# DigitMux.net
KiCad netlist of a schematic drawn in EAGLE
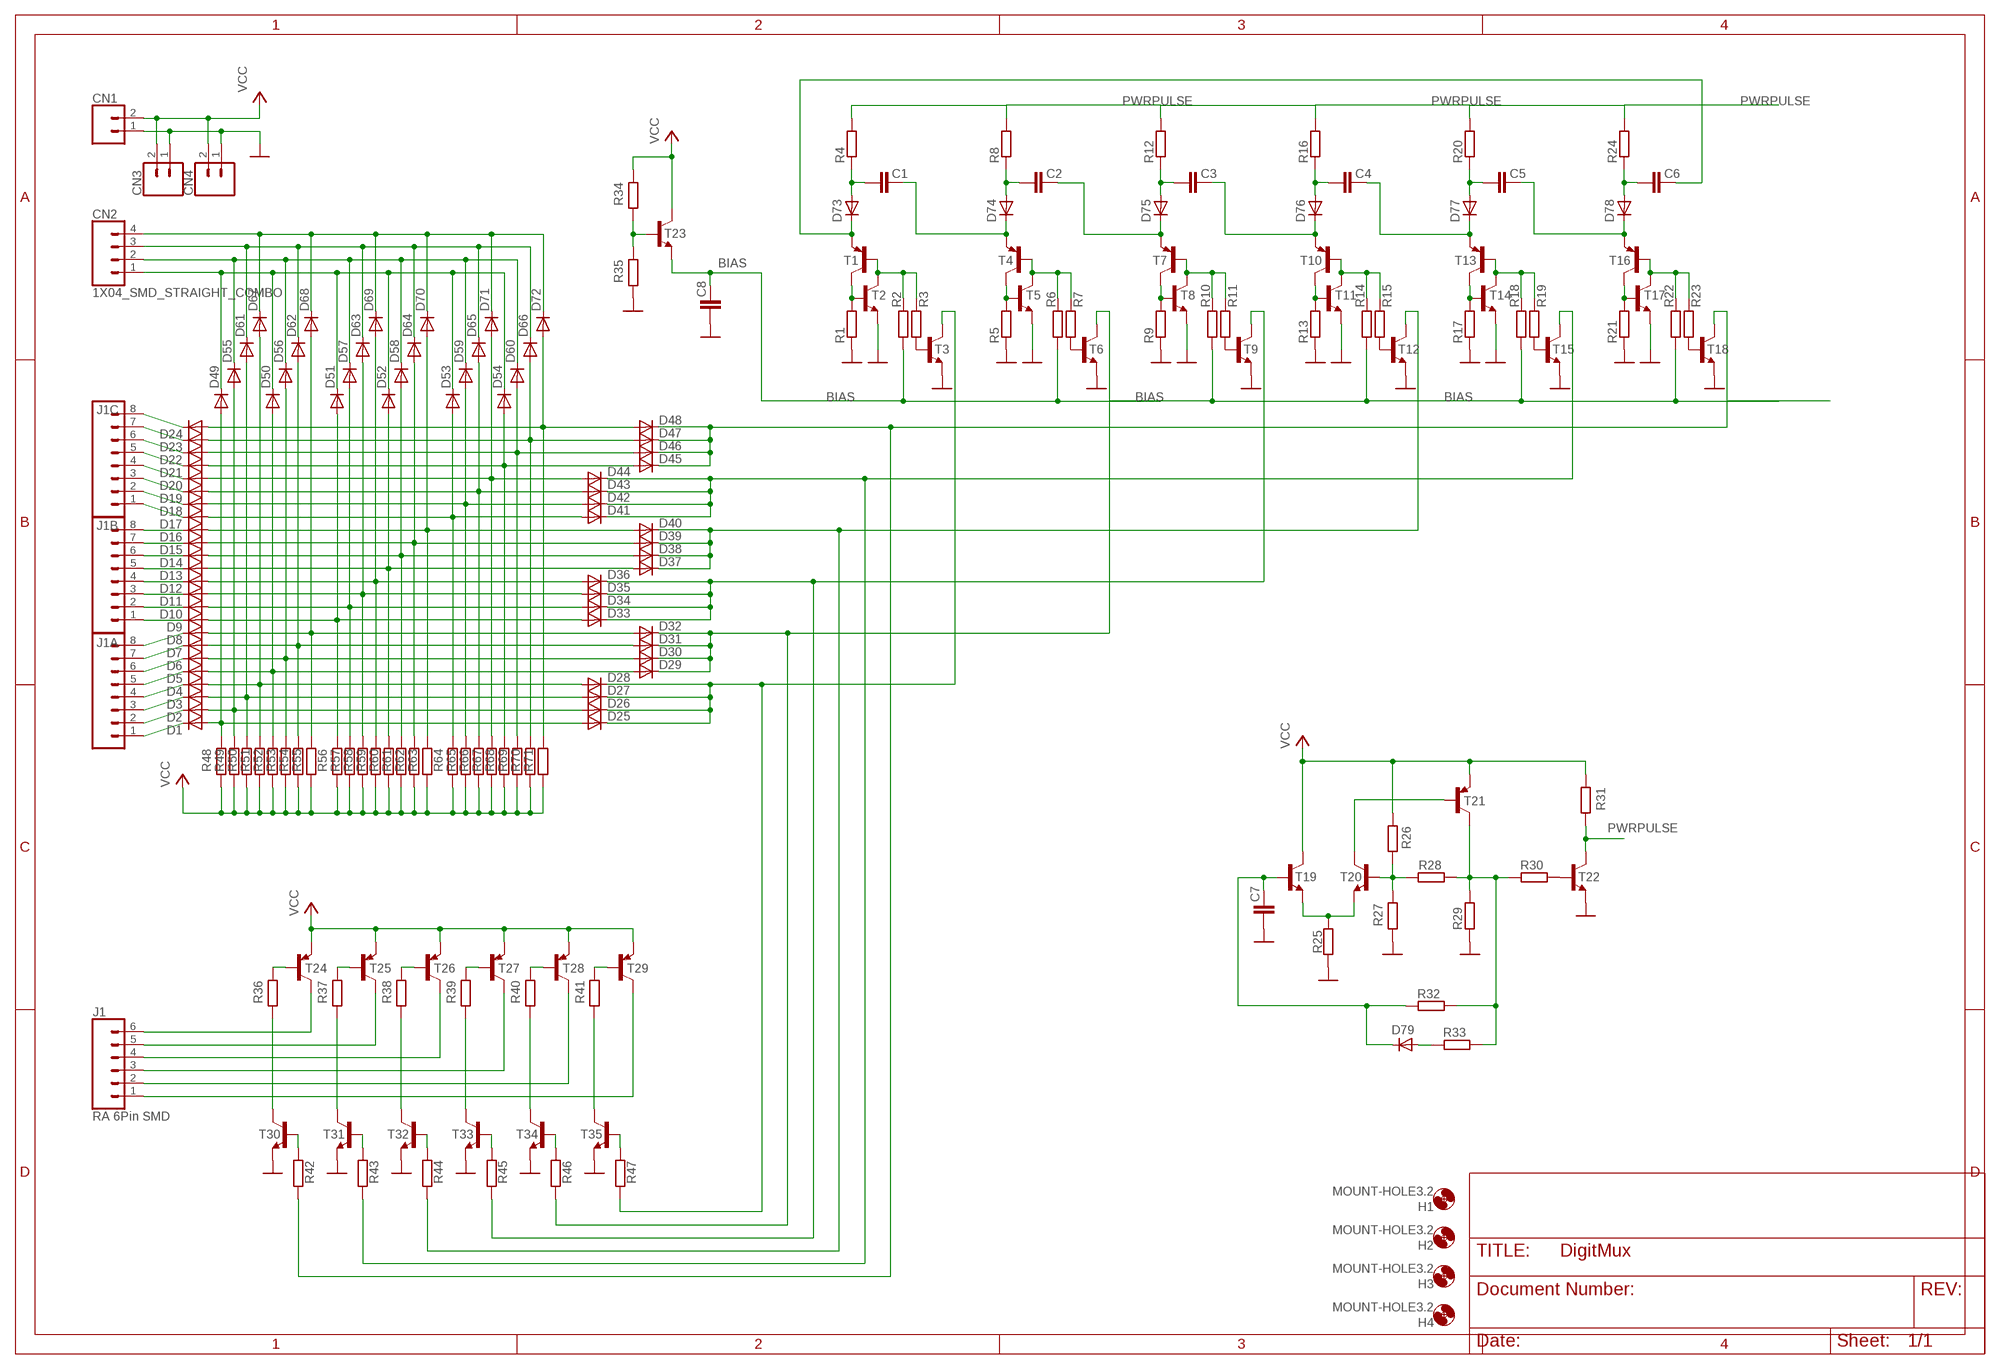
[diagram p0: schematic, sheet 1]

(export (version "E")
  (design (tool "Eeschema 10.0.6"))
  (components
    (comp (ref "C1")
      (value "0.1uF")
      (footprint "eagle-import:CAP-PTH-SMALL-KIT")
      (libsource (lib "eagle-import") (part "0.1UF-KIT-EZ-50V-20%"))
    )
    (comp (ref "C2")
      (value "0.1uF")
      (footprint "eagle-import:CAP-PTH-SMALL-KIT")
      (libsource (lib "eagle-import") (part "0.1UF-KIT-EZ-50V-20%"))
    )
    (comp (ref "C3")
      (value "0.1uF")
      (footprint "eagle-import:CAP-PTH-SMALL-KIT")
      (libsource (lib "eagle-import") (part "0.1UF-KIT-EZ-50V-20%"))
    )
    (comp (ref "C4")
      (value "0.1uF")
      (footprint "eagle-import:CAP-PTH-SMALL-KIT")
      (libsource (lib "eagle-import") (part "0.1UF-KIT-EZ-50V-20%"))
    )
    (comp (ref "C5")
      (value "0.1uF")
      (footprint "eagle-import:CAP-PTH-SMALL-KIT")
      (libsource (lib "eagle-import") (part "0.1UF-KIT-EZ-50V-20%"))
    )
    (comp (ref "C6")
      (value "0.1uF")
      (footprint "eagle-import:CAP-PTH-SMALL-KIT")
      (libsource (lib "eagle-import") (part "0.1UF-KIT-EZ-50V-20%"))
    )
    (comp (ref "C7")
      (value "0.1uF")
      (footprint "eagle-import:CAP-PTH-SMALL-KIT")
      (libsource (lib "eagle-import") (part "0.1UF-KIT-EZ-50V-20%"))
    )
    (comp (ref "C8")
      (value "0.1uF")
      (footprint "eagle-import:CAP-PTH-SMALL-KIT")
      (libsource (lib "eagle-import") (part "0.1UF-KIT-EZ-50V-20%"))
    )
    (comp (ref "CN1")
      (value "CONN_02")
      (footprint "eagle-import:1X02")
      (libsource (lib "eagle-import") (part "CONN_02"))
    )
    (comp (ref "CN2")
      (value "1X04_SMD_STRAIGHT_COMBO")
      (footprint "eagle-import:1X04")
      (libsource (lib "eagle-import") (part "CONN_04"))
    )
    (comp (ref "CN3")
      (value "CONN_02")
      (footprint "eagle-import:1X02")
      (libsource (lib "eagle-import") (part "CONN_02"))
    )
    (comp (ref "CN4")
      (value "CONN_02")
      (footprint "eagle-import:1X02")
      (libsource (lib "eagle-import") (part "CONN_02"))
    )
    (comp (ref "D1")
      (value "SMALL_DIODEDO35-7")
      (footprint "eagle-import:DO35-7")
      (libsource (lib "eagle-import") (part "SMALL_DIODEDO35-7"))
    )
    (comp (ref "D2")
      (value "SMALL_DIODEDO35-7")
      (footprint "eagle-import:DO35-7")
      (libsource (lib "eagle-import") (part "SMALL_DIODEDO35-7"))
    )
    (comp (ref "D3")
      (value "SMALL_DIODEDO35-7")
      (footprint "eagle-import:DO35-7")
      (libsource (lib "eagle-import") (part "SMALL_DIODEDO35-7"))
    )
    (comp (ref "D4")
      (value "SMALL_DIODEDO35-7")
      (footprint "eagle-import:DO35-7")
      (libsource (lib "eagle-import") (part "SMALL_DIODEDO35-7"))
    )
    (comp (ref "D5")
      (value "SMALL_DIODEDO35-7")
      (footprint "eagle-import:DO35-7")
      (libsource (lib "eagle-import") (part "SMALL_DIODEDO35-7"))
    )
    (comp (ref "D6")
      (value "SMALL_DIODEDO35-7")
      (footprint "eagle-import:DO35-7")
      (libsource (lib "eagle-import") (part "SMALL_DIODEDO35-7"))
    )
    (comp (ref "D7")
      (value "SMALL_DIODEDO35-7")
      (footprint "eagle-import:DO35-7")
      (libsource (lib "eagle-import") (part "SMALL_DIODEDO35-7"))
    )
    (comp (ref "D8")
      (value "SMALL_DIODEDO35-7")
      (footprint "eagle-import:DO35-7")
      (libsource (lib "eagle-import") (part "SMALL_DIODEDO35-7"))
    )
    (comp (ref "D9")
      (value "SMALL_DIODEDO35-7")
      (footprint "eagle-import:DO35-7")
      (libsource (lib "eagle-import") (part "SMALL_DIODEDO35-7"))
    )
    (comp (ref "D10")
      (value "SMALL_DIODEDO35-7")
      (footprint "eagle-import:DO35-7")
      (libsource (lib "eagle-import") (part "SMALL_DIODEDO35-7"))
    )
    (comp (ref "D11")
      (value "SMALL_DIODEDO35-7")
      (footprint "eagle-import:DO35-7")
      (libsource (lib "eagle-import") (part "SMALL_DIODEDO35-7"))
    )
    (comp (ref "D12")
      (value "SMALL_DIODEDO35-7")
      (footprint "eagle-import:DO35-7")
      (libsource (lib "eagle-import") (part "SMALL_DIODEDO35-7"))
    )
    (comp (ref "D13")
      (value "SMALL_DIODEDO35-7")
      (footprint "eagle-import:DO35-7")
      (libsource (lib "eagle-import") (part "SMALL_DIODEDO35-7"))
    )
    (comp (ref "D14")
      (value "SMALL_DIODEDO35-7")
      (footprint "eagle-import:DO35-7")
      (libsource (lib "eagle-import") (part "SMALL_DIODEDO35-7"))
    )
    (comp (ref "D15")
      (value "SMALL_DIODEDO35-7")
      (footprint "eagle-import:DO35-7")
      (libsource (lib "eagle-import") (part "SMALL_DIODEDO35-7"))
    )
    (comp (ref "D16")
      (value "SMALL_DIODEDO35-7")
      (footprint "eagle-import:DO35-7")
      (libsource (lib "eagle-import") (part "SMALL_DIODEDO35-7"))
    )
    (comp (ref "D17")
      (value "SMALL_DIODEDO35-7")
      (footprint "eagle-import:DO35-7")
      (libsource (lib "eagle-import") (part "SMALL_DIODEDO35-7"))
    )
    (comp (ref "D18")
      (value "SMALL_DIODEDO35-7")
      (footprint "eagle-import:DO35-7")
      (libsource (lib "eagle-import") (part "SMALL_DIODEDO35-7"))
    )
    (comp (ref "D19")
      (value "SMALL_DIODEDO35-7")
      (footprint "eagle-import:DO35-7")
      (libsource (lib "eagle-import") (part "SMALL_DIODEDO35-7"))
    )
    (comp (ref "D20")
      (value "SMALL_DIODEDO35-7")
      (footprint "eagle-import:DO35-7")
      (libsource (lib "eagle-import") (part "SMALL_DIODEDO35-7"))
    )
    (comp (ref "D21")
      (value "SMALL_DIODEDO35-7")
      (footprint "eagle-import:DO35-7")
      (libsource (lib "eagle-import") (part "SMALL_DIODEDO35-7"))
    )
    (comp (ref "D22")
      (value "SMALL_DIODEDO35-7")
      (footprint "eagle-import:DO35-7")
      (libsource (lib "eagle-import") (part "SMALL_DIODEDO35-7"))
    )
    (comp (ref "D23")
      (value "SMALL_DIODEDO35-7")
      (footprint "eagle-import:DO35-7")
      (libsource (lib "eagle-import") (part "SMALL_DIODEDO35-7"))
    )
    (comp (ref "D24")
      (value "SMALL_DIODEDO35-7")
      (footprint "eagle-import:DO35-7")
      (libsource (lib "eagle-import") (part "SMALL_DIODEDO35-7"))
    )
    (comp (ref "D25")
      (value "SMALL_DIODEDO35-7")
      (footprint "eagle-import:DO35-7")
      (libsource (lib "eagle-import") (part "SMALL_DIODEDO35-7"))
    )
    (comp (ref "D26")
      (value "SMALL_DIODEDO35-7")
      (footprint "eagle-import:DO35-7")
      (libsource (lib "eagle-import") (part "SMALL_DIODEDO35-7"))
    )
    (comp (ref "D27")
      (value "SMALL_DIODEDO35-7")
      (footprint "eagle-import:DO35-7")
      (libsource (lib "eagle-import") (part "SMALL_DIODEDO35-7"))
    )
    (comp (ref "D28")
      (value "SMALL_DIODEDO35-7")
      (footprint "eagle-import:DO35-7")
      (libsource (lib "eagle-import") (part "SMALL_DIODEDO35-7"))
    )
    (comp (ref "D29")
      (value "SMALL_DIODEDO35-7")
      (footprint "eagle-import:DO35-7")
      (libsource (lib "eagle-import") (part "SMALL_DIODEDO35-7"))
    )
    (comp (ref "D30")
      (value "SMALL_DIODEDO35-7")
      (footprint "eagle-import:DO35-7")
      (libsource (lib "eagle-import") (part "SMALL_DIODEDO35-7"))
    )
    (comp (ref "D31")
      (value "SMALL_DIODEDO35-7")
      (footprint "eagle-import:DO35-7")
      (libsource (lib "eagle-import") (part "SMALL_DIODEDO35-7"))
    )
    (comp (ref "D32")
      (value "SMALL_DIODEDO35-7")
      (footprint "eagle-import:DO35-7")
      (libsource (lib "eagle-import") (part "SMALL_DIODEDO35-7"))
    )
    (comp (ref "D33")
      (value "SMALL_DIODEDO35-7")
      (footprint "eagle-import:DO35-7")
      (libsource (lib "eagle-import") (part "SMALL_DIODEDO35-7"))
    )
    (comp (ref "D34")
      (value "SMALL_DIODEDO35-7")
      (footprint "eagle-import:DO35-7")
      (libsource (lib "eagle-import") (part "SMALL_DIODEDO35-7"))
    )
    (comp (ref "D35")
      (value "SMALL_DIODEDO35-7")
      (footprint "eagle-import:DO35-7")
      (libsource (lib "eagle-import") (part "SMALL_DIODEDO35-7"))
    )
    (comp (ref "D36")
      (value "SMALL_DIODEDO35-7")
      (footprint "eagle-import:DO35-7")
      (libsource (lib "eagle-import") (part "SMALL_DIODEDO35-7"))
    )
    (comp (ref "D37")
      (value "SMALL_DIODEDO35-7")
      (footprint "eagle-import:DO35-7")
      (libsource (lib "eagle-import") (part "SMALL_DIODEDO35-7"))
    )
    (comp (ref "D38")
      (value "SMALL_DIODEDO35-7")
      (footprint "eagle-import:DO35-7")
      (libsource (lib "eagle-import") (part "SMALL_DIODEDO35-7"))
    )
    (comp (ref "D39")
      (value "SMALL_DIODEDO35-7")
      (footprint "eagle-import:DO35-7")
      (libsource (lib "eagle-import") (part "SMALL_DIODEDO35-7"))
    )
    (comp (ref "D40")
      (value "SMALL_DIODEDO35-7")
      (footprint "eagle-import:DO35-7")
      (libsource (lib "eagle-import") (part "SMALL_DIODEDO35-7"))
    )
    (comp (ref "D41")
      (value "SMALL_DIODEDO35-7")
      (footprint "eagle-import:DO35-7")
      (libsource (lib "eagle-import") (part "SMALL_DIODEDO35-7"))
    )
    (comp (ref "D42")
      (value "SMALL_DIODEDO35-7")
      (footprint "eagle-import:DO35-7")
      (libsource (lib "eagle-import") (part "SMALL_DIODEDO35-7"))
    )
    (comp (ref "D43")
      (value "SMALL_DIODEDO35-7")
      (footprint "eagle-import:DO35-7")
      (libsource (lib "eagle-import") (part "SMALL_DIODEDO35-7"))
    )
    (comp (ref "D44")
      (value "SMALL_DIODEDO35-7")
      (footprint "eagle-import:DO35-7")
      (libsource (lib "eagle-import") (part "SMALL_DIODEDO35-7"))
    )
    (comp (ref "D45")
      (value "SMALL_DIODEDO35-7")
      (footprint "eagle-import:DO35-7")
      (libsource (lib "eagle-import") (part "SMALL_DIODEDO35-7"))
    )
    (comp (ref "D46")
      (value "SMALL_DIODEDO35-7")
      (footprint "eagle-import:DO35-7")
      (libsource (lib "eagle-import") (part "SMALL_DIODEDO35-7"))
    )
    (comp (ref "D47")
      (value "SMALL_DIODEDO35-7")
      (footprint "eagle-import:DO35-7")
      (libsource (lib "eagle-import") (part "SMALL_DIODEDO35-7"))
    )
    (comp (ref "D48")
      (value "SMALL_DIODEDO35-7")
      (footprint "eagle-import:DO35-7")
      (libsource (lib "eagle-import") (part "SMALL_DIODEDO35-7"))
    )
    (comp (ref "D49")
      (value "SMALL_DIODEDO35-7")
      (footprint "eagle-import:DO35-7")
      (libsource (lib "eagle-import") (part "SMALL_DIODEDO35-7"))
    )
    (comp (ref "D50")
      (value "SMALL_DIODEDO35-7")
      (footprint "eagle-import:DO35-7")
      (libsource (lib "eagle-import") (part "SMALL_DIODEDO35-7"))
    )
    (comp (ref "D51")
      (value "SMALL_DIODEDO35-7")
      (footprint "eagle-import:DO35-7")
      (libsource (lib "eagle-import") (part "SMALL_DIODEDO35-7"))
    )
    (comp (ref "D52")
      (value "SMALL_DIODEDO35-7")
      (footprint "eagle-import:DO35-7")
      (libsource (lib "eagle-import") (part "SMALL_DIODEDO35-7"))
    )
    (comp (ref "D53")
      (value "SMALL_DIODEDO35-7")
      (footprint "eagle-import:DO35-7")
      (libsource (lib "eagle-import") (part "SMALL_DIODEDO35-7"))
    )
    (comp (ref "D54")
      (value "SMALL_DIODEDO35-7")
      (footprint "eagle-import:DO35-7")
      (libsource (lib "eagle-import") (part "SMALL_DIODEDO35-7"))
    )
    (comp (ref "D55")
      (value "SMALL_DIODEDO35-7")
      (footprint "eagle-import:DO35-7")
      (libsource (lib "eagle-import") (part "SMALL_DIODEDO35-7"))
    )
    (comp (ref "D56")
      (value "SMALL_DIODEDO35-7")
      (footprint "eagle-import:DO35-7")
      (libsource (lib "eagle-import") (part "SMALL_DIODEDO35-7"))
    )
    (comp (ref "D57")
      (value "SMALL_DIODEDO35-7")
      (footprint "eagle-import:DO35-7")
      (libsource (lib "eagle-import") (part "SMALL_DIODEDO35-7"))
    )
    (comp (ref "D58")
      (value "SMALL_DIODEDO35-7")
      (footprint "eagle-import:DO35-7")
      (libsource (lib "eagle-import") (part "SMALL_DIODEDO35-7"))
    )
    (comp (ref "D59")
      (value "SMALL_DIODEDO35-7")
      (footprint "eagle-import:DO35-7")
      (libsource (lib "eagle-import") (part "SMALL_DIODEDO35-7"))
    )
    (comp (ref "D60")
      (value "SMALL_DIODEDO35-7")
      (footprint "eagle-import:DO35-7")
      (libsource (lib "eagle-import") (part "SMALL_DIODEDO35-7"))
    )
    (comp (ref "D61")
      (value "SMALL_DIODEDO35-7")
      (footprint "eagle-import:DO35-7")
      (libsource (lib "eagle-import") (part "SMALL_DIODEDO35-7"))
    )
    (comp (ref "D62")
      (value "SMALL_DIODEDO35-7")
      (footprint "eagle-import:DO35-7")
      (libsource (lib "eagle-import") (part "SMALL_DIODEDO35-7"))
    )
    (comp (ref "D63")
      (value "SMALL_DIODEDO35-7")
      (footprint "eagle-import:DO35-7")
      (libsource (lib "eagle-import") (part "SMALL_DIODEDO35-7"))
    )
    (comp (ref "D64")
      (value "SMALL_DIODEDO35-7")
      (footprint "eagle-import:DO35-7")
      (libsource (lib "eagle-import") (part "SMALL_DIODEDO35-7"))
    )
    (comp (ref "D65")
      (value "SMALL_DIODEDO35-7")
      (footprint "eagle-import:DO35-7")
      (libsource (lib "eagle-import") (part "SMALL_DIODEDO35-7"))
    )
    (comp (ref "D66")
      (value "SMALL_DIODEDO35-7")
      (footprint "eagle-import:DO35-7")
      (libsource (lib "eagle-import") (part "SMALL_DIODEDO35-7"))
    )
    (comp (ref "D67")
      (value "SMALL_DIODEDO35-7")
      (footprint "eagle-import:DO35-7")
      (libsource (lib "eagle-import") (part "SMALL_DIODEDO35-7"))
    )
    (comp (ref "D68")
      (value "SMALL_DIODEDO35-7")
      (footprint "eagle-import:DO35-7")
      (libsource (lib "eagle-import") (part "SMALL_DIODEDO35-7"))
    )
    (comp (ref "D69")
      (value "SMALL_DIODEDO35-7")
      (footprint "eagle-import:DO35-7")
      (libsource (lib "eagle-import") (part "SMALL_DIODEDO35-7"))
    )
    (comp (ref "D70")
      (value "SMALL_DIODEDO35-7")
      (footprint "eagle-import:DO35-7")
      (libsource (lib "eagle-import") (part "SMALL_DIODEDO35-7"))
    )
    (comp (ref "D71")
      (value "SMALL_DIODEDO35-7")
      (footprint "eagle-import:DO35-7")
      (libsource (lib "eagle-import") (part "SMALL_DIODEDO35-7"))
    )
    (comp (ref "D72")
      (value "SMALL_DIODEDO35-7")
      (footprint "eagle-import:DO35-7")
      (libsource (lib "eagle-import") (part "SMALL_DIODEDO35-7"))
    )
    (comp (ref "D73")
      (value "SMALL_DIODEDO35-7")
      (footprint "eagle-import:DO35-7")
      (libsource (lib "eagle-import") (part "SMALL_DIODEDO35-7"))
    )
    (comp (ref "D74")
      (value "SMALL_DIODEDO35-7")
      (footprint "eagle-import:DO35-7")
      (libsource (lib "eagle-import") (part "SMALL_DIODEDO35-7"))
    )
    (comp (ref "D75")
      (value "SMALL_DIODEDO35-7")
      (footprint "eagle-import:DO35-7")
      (libsource (lib "eagle-import") (part "SMALL_DIODEDO35-7"))
    )
    (comp (ref "D76")
      (value "SMALL_DIODEDO35-7")
      (footprint "eagle-import:DO35-7")
      (libsource (lib "eagle-import") (part "SMALL_DIODEDO35-7"))
    )
    (comp (ref "D77")
      (value "SMALL_DIODEDO35-7")
      (footprint "eagle-import:DO35-7")
      (libsource (lib "eagle-import") (part "SMALL_DIODEDO35-7"))
    )
    (comp (ref "D78")
      (value "SMALL_DIODEDO35-7")
      (footprint "eagle-import:DO35-7")
      (libsource (lib "eagle-import") (part "SMALL_DIODEDO35-7"))
    )
    (comp (ref "D79")
      (value "SMALL_DIODEDO35-7")
      (footprint "eagle-import:DO35-7")
      (libsource (lib "eagle-import") (part "SMALL_DIODEDO35-7"))
    )
    (comp (ref "H1")
      (value "MOUNT-HOLE3.2")
      (footprint "eagle-import:3,2")
      (libsource (lib "eagle-import") (part "MOUNT-HOLE3.2"))
    )
    (comp (ref "H2")
      (value "MOUNT-HOLE3.2")
      (footprint "eagle-import:3,2")
      (libsource (lib "eagle-import") (part "MOUNT-HOLE3.2"))
    )
    (comp (ref "H3")
      (value "MOUNT-HOLE3.2")
      (footprint "eagle-import:3,2")
      (libsource (lib "eagle-import") (part "MOUNT-HOLE3.2"))
    )
    (comp (ref "H4")
      (value "MOUNT-HOLE3.2")
      (footprint "eagle-import:3,2")
      (libsource (lib "eagle-import") (part "MOUNT-HOLE3.2"))
    )
    (comp (ref "J1")
      (value "RA 6Pin SMD")
      (footprint "eagle-import:1X06")
      (libsource (lib "eagle-import") (part "CONN_06SILK_FEMALE_PTH"))
    )
    (comp (ref "J1A")
      (value "CONN_08\"")
      (footprint "eagle-import:1X08")
      (libsource (lib "eagle-import") (part "CONN_08{dblquote}"))
    )
    (comp (ref "J1B")
      (value "CONN_08\"")
      (footprint "eagle-import:1X08")
      (libsource (lib "eagle-import") (part "CONN_08{dblquote}"))
    )
    (comp (ref "J1C")
      (value "CONN_08\"")
      (footprint "eagle-import:1X08")
      (libsource (lib "eagle-import") (part "CONN_08{dblquote}"))
    )
    (comp (ref "R1")
      (value "RESISTOR7MM")
      (footprint "eagle-import:7MM_RESISTOR")
      (libsource (lib "eagle-import") (part "RESISTOR7MM"))
    )
    (comp (ref "R2")
      (value "RESISTOR7MM")
      (footprint "eagle-import:7MM_RESISTOR")
      (libsource (lib "eagle-import") (part "RESISTOR7MM"))
    )
    (comp (ref "R3")
      (value "RESISTOR7MM")
      (footprint "eagle-import:7MM_RESISTOR")
      (libsource (lib "eagle-import") (part "RESISTOR7MM"))
    )
    (comp (ref "R4")
      (value "RESISTOR7MM")
      (footprint "eagle-import:7MM_RESISTOR")
      (libsource (lib "eagle-import") (part "RESISTOR7MM"))
    )
    (comp (ref "R5")
      (value "RESISTOR7MM")
      (footprint "eagle-import:7MM_RESISTOR")
      (libsource (lib "eagle-import") (part "RESISTOR7MM"))
    )
    (comp (ref "R6")
      (value "RESISTOR7MM")
      (footprint "eagle-import:7MM_RESISTOR")
      (libsource (lib "eagle-import") (part "RESISTOR7MM"))
    )
    (comp (ref "R7")
      (value "RESISTOR7MM")
      (footprint "eagle-import:7MM_RESISTOR")
      (libsource (lib "eagle-import") (part "RESISTOR7MM"))
    )
    (comp (ref "R8")
      (value "RESISTOR7MM")
      (footprint "eagle-import:7MM_RESISTOR")
      (libsource (lib "eagle-import") (part "RESISTOR7MM"))
    )
    (comp (ref "R9")
      (value "RESISTOR7MM")
      (footprint "eagle-import:7MM_RESISTOR")
      (libsource (lib "eagle-import") (part "RESISTOR7MM"))
    )
    (comp (ref "R10")
      (value "RESISTOR7MM")
      (footprint "eagle-import:7MM_RESISTOR")
      (libsource (lib "eagle-import") (part "RESISTOR7MM"))
    )
    (comp (ref "R11")
      (value "RESISTOR7MM")
      (footprint "eagle-import:7MM_RESISTOR")
      (libsource (lib "eagle-import") (part "RESISTOR7MM"))
    )
    (comp (ref "R12")
      (value "RESISTOR7MM")
      (footprint "eagle-import:7MM_RESISTOR")
      (libsource (lib "eagle-import") (part "RESISTOR7MM"))
    )
    (comp (ref "R13")
      (value "RESISTOR7MM")
      (footprint "eagle-import:7MM_RESISTOR")
      (libsource (lib "eagle-import") (part "RESISTOR7MM"))
    )
    (comp (ref "R14")
      (value "RESISTOR7MM")
      (footprint "eagle-import:7MM_RESISTOR")
      (libsource (lib "eagle-import") (part "RESISTOR7MM"))
    )
    (comp (ref "R15")
      (value "RESISTOR7MM")
      (footprint "eagle-import:7MM_RESISTOR")
      (libsource (lib "eagle-import") (part "RESISTOR7MM"))
    )
    (comp (ref "R16")
      (value "RESISTOR7MM")
      (footprint "eagle-import:7MM_RESISTOR")
      (libsource (lib "eagle-import") (part "RESISTOR7MM"))
    )
    (comp (ref "R17")
      (value "RESISTOR7MM")
      (footprint "eagle-import:7MM_RESISTOR")
      (libsource (lib "eagle-import") (part "RESISTOR7MM"))
    )
    (comp (ref "R18")
      (value "RESISTOR7MM")
      (footprint "eagle-import:7MM_RESISTOR")
      (libsource (lib "eagle-import") (part "RESISTOR7MM"))
    )
    (comp (ref "R19")
      (value "RESISTOR7MM")
      (footprint "eagle-import:7MM_RESISTOR")
      (libsource (lib "eagle-import") (part "RESISTOR7MM"))
    )
    (comp (ref "R20")
      (value "RESISTOR7MM")
      (footprint "eagle-import:7MM_RESISTOR")
      (libsource (lib "eagle-import") (part "RESISTOR7MM"))
    )
    (comp (ref "R21")
      (value "RESISTOR7MM")
      (footprint "eagle-import:7MM_RESISTOR")
      (libsource (lib "eagle-import") (part "RESISTOR7MM"))
    )
    (comp (ref "R22")
      (value "RESISTOR7MM")
      (footprint "eagle-import:7MM_RESISTOR")
      (libsource (lib "eagle-import") (part "RESISTOR7MM"))
    )
    (comp (ref "R23")
      (value "RESISTOR7MM")
      (footprint "eagle-import:7MM_RESISTOR")
      (libsource (lib "eagle-import") (part "RESISTOR7MM"))
    )
    (comp (ref "R24")
      (value "RESISTOR7MM")
      (footprint "eagle-import:7MM_RESISTOR")
      (libsource (lib "eagle-import") (part "RESISTOR7MM"))
    )
    (comp (ref "R25")
      (value "RESISTOR7MM")
      (footprint "eagle-import:7MM_RESISTOR")
      (libsource (lib "eagle-import") (part "RESISTOR7MM"))
    )
    (comp (ref "R26")
      (value "RESISTOR7MM")
      (footprint "eagle-import:7MM_RESISTOR")
      (libsource (lib "eagle-import") (part "RESISTOR7MM"))
    )
    (comp (ref "R27")
      (value "RESISTOR7MM")
      (footprint "eagle-import:7MM_RESISTOR")
      (libsource (lib "eagle-import") (part "RESISTOR7MM"))
    )
    (comp (ref "R28")
      (value "RESISTOR7MM")
      (footprint "eagle-import:7MM_RESISTOR")
      (libsource (lib "eagle-import") (part "RESISTOR7MM"))
    )
    (comp (ref "R29")
      (value "RESISTOR7MM")
      (footprint "eagle-import:7MM_RESISTOR")
      (libsource (lib "eagle-import") (part "RESISTOR7MM"))
    )
    (comp (ref "R30")
      (value "RESISTOR7MM")
      (footprint "eagle-import:7MM_RESISTOR")
      (libsource (lib "eagle-import") (part "RESISTOR7MM"))
    )
    (comp (ref "R31")
      (value "RESISTOR7MM")
      (footprint "eagle-import:7MM_RESISTOR")
      (libsource (lib "eagle-import") (part "RESISTOR7MM"))
    )
    (comp (ref "R32")
      (value "RESISTOR7MM")
      (footprint "eagle-import:7MM_RESISTOR")
      (libsource (lib "eagle-import") (part "RESISTOR7MM"))
    )
    (comp (ref "R33")
      (value "RESISTOR7MM")
      (footprint "eagle-import:7MM_RESISTOR")
      (libsource (lib "eagle-import") (part "RESISTOR7MM"))
    )
    (comp (ref "R34")
      (value "RESISTOR7MM")
      (footprint "eagle-import:7MM_RESISTOR")
      (libsource (lib "eagle-import") (part "RESISTOR7MM"))
    )
    (comp (ref "R35")
      (value "RESISTOR7MM")
      (footprint "eagle-import:7MM_RESISTOR")
      (libsource (lib "eagle-import") (part "RESISTOR7MM"))
    )
    (comp (ref "R36")
      (value "RESISTOR7MM")
      (footprint "eagle-import:7MM_RESISTOR")
      (libsource (lib "eagle-import") (part "RESISTOR7MM"))
    )
    (comp (ref "R37")
      (value "RESISTOR7MM")
      (footprint "eagle-import:7MM_RESISTOR")
      (libsource (lib "eagle-import") (part "RESISTOR7MM"))
    )
    (comp (ref "R38")
      (value "RESISTOR7MM")
      (footprint "eagle-import:7MM_RESISTOR")
      (libsource (lib "eagle-import") (part "RESISTOR7MM"))
    )
    (comp (ref "R39")
      (value "RESISTOR7MM")
      (footprint "eagle-import:7MM_RESISTOR")
      (libsource (lib "eagle-import") (part "RESISTOR7MM"))
    )
    (comp (ref "R40")
      (value "RESISTOR7MM")
      (footprint "eagle-import:7MM_RESISTOR")
      (libsource (lib "eagle-import") (part "RESISTOR7MM"))
    )
    (comp (ref "R41")
      (value "RESISTOR7MM")
      (footprint "eagle-import:7MM_RESISTOR")
      (libsource (lib "eagle-import") (part "RESISTOR7MM"))
    )
    (comp (ref "R42")
      (value "RESISTOR7MM")
      (footprint "eagle-import:7MM_RESISTOR")
      (libsource (lib "eagle-import") (part "RESISTOR7MM"))
    )
    (comp (ref "R43")
      (value "RESISTOR7MM")
      (footprint "eagle-import:7MM_RESISTOR")
      (libsource (lib "eagle-import") (part "RESISTOR7MM"))
    )
    (comp (ref "R44")
      (value "RESISTOR7MM")
      (footprint "eagle-import:7MM_RESISTOR")
      (libsource (lib "eagle-import") (part "RESISTOR7MM"))
    )
    (comp (ref "R45")
      (value "RESISTOR7MM")
      (footprint "eagle-import:7MM_RESISTOR")
      (libsource (lib "eagle-import") (part "RESISTOR7MM"))
    )
    (comp (ref "R46")
      (value "RESISTOR7MM")
      (footprint "eagle-import:7MM_RESISTOR")
      (libsource (lib "eagle-import") (part "RESISTOR7MM"))
    )
    (comp (ref "R47")
      (value "RESISTOR7MM")
      (footprint "eagle-import:7MM_RESISTOR")
      (libsource (lib "eagle-import") (part "RESISTOR7MM"))
    )
    (comp (ref "R48")
      (value "RESISTOR7MM")
      (footprint "eagle-import:7MM_RESISTOR")
      (libsource (lib "eagle-import") (part "RESISTOR7MM"))
    )
    (comp (ref "R49")
      (value "RESISTOR7MM")
      (footprint "eagle-import:7MM_RESISTOR")
      (libsource (lib "eagle-import") (part "RESISTOR7MM"))
    )
    (comp (ref "R50")
      (value "RESISTOR7MM")
      (footprint "eagle-import:7MM_RESISTOR")
      (libsource (lib "eagle-import") (part "RESISTOR7MM"))
    )
    (comp (ref "R51")
      (value "RESISTOR7MM")
      (footprint "eagle-import:7MM_RESISTOR")
      (libsource (lib "eagle-import") (part "RESISTOR7MM"))
    )
    (comp (ref "R52")
      (value "RESISTOR7MM")
      (footprint "eagle-import:7MM_RESISTOR")
      (libsource (lib "eagle-import") (part "RESISTOR7MM"))
    )
    (comp (ref "R53")
      (value "RESISTOR7MM")
      (footprint "eagle-import:7MM_RESISTOR")
      (libsource (lib "eagle-import") (part "RESISTOR7MM"))
    )
    (comp (ref "R54")
      (value "RESISTOR7MM")
      (footprint "eagle-import:7MM_RESISTOR")
      (libsource (lib "eagle-import") (part "RESISTOR7MM"))
    )
    (comp (ref "R55")
      (value "RESISTOR7MM")
      (footprint "eagle-import:7MM_RESISTOR")
      (libsource (lib "eagle-import") (part "RESISTOR7MM"))
    )
    (comp (ref "R56")
      (value "RESISTOR7MM")
      (footprint "eagle-import:7MM_RESISTOR")
      (libsource (lib "eagle-import") (part "RESISTOR7MM"))
    )
    (comp (ref "R57")
      (value "RESISTOR7MM")
      (footprint "eagle-import:7MM_RESISTOR")
      (libsource (lib "eagle-import") (part "RESISTOR7MM"))
    )
    (comp (ref "R58")
      (value "RESISTOR7MM")
      (footprint "eagle-import:7MM_RESISTOR")
      (libsource (lib "eagle-import") (part "RESISTOR7MM"))
    )
    (comp (ref "R59")
      (value "RESISTOR7MM")
      (footprint "eagle-import:7MM_RESISTOR")
      (libsource (lib "eagle-import") (part "RESISTOR7MM"))
    )
    (comp (ref "R60")
      (value "RESISTOR7MM")
      (footprint "eagle-import:7MM_RESISTOR")
      (libsource (lib "eagle-import") (part "RESISTOR7MM"))
    )
    (comp (ref "R61")
      (value "RESISTOR7MM")
      (footprint "eagle-import:7MM_RESISTOR")
      (libsource (lib "eagle-import") (part "RESISTOR7MM"))
    )
    (comp (ref "R62")
      (value "RESISTOR7MM")
      (footprint "eagle-import:7MM_RESISTOR")
      (libsource (lib "eagle-import") (part "RESISTOR7MM"))
    )
    (comp (ref "R63")
      (value "RESISTOR7MM")
      (footprint "eagle-import:7MM_RESISTOR")
      (libsource (lib "eagle-import") (part "RESISTOR7MM"))
    )
    (comp (ref "R64")
      (value "RESISTOR7MM")
      (footprint "eagle-import:7MM_RESISTOR")
      (libsource (lib "eagle-import") (part "RESISTOR7MM"))
    )
    (comp (ref "R65")
      (value "RESISTOR7MM")
      (footprint "eagle-import:7MM_RESISTOR")
      (libsource (lib "eagle-import") (part "RESISTOR7MM"))
    )
    (comp (ref "R66")
      (value "RESISTOR7MM")
      (footprint "eagle-import:7MM_RESISTOR")
      (libsource (lib "eagle-import") (part "RESISTOR7MM"))
    )
    (comp (ref "R67")
      (value "RESISTOR7MM")
      (footprint "eagle-import:7MM_RESISTOR")
      (libsource (lib "eagle-import") (part "RESISTOR7MM"))
    )
    (comp (ref "R68")
      (value "RESISTOR7MM")
      (footprint "eagle-import:7MM_RESISTOR")
      (libsource (lib "eagle-import") (part "RESISTOR7MM"))
    )
    (comp (ref "R69")
      (value "RESISTOR7MM")
      (footprint "eagle-import:7MM_RESISTOR")
      (libsource (lib "eagle-import") (part "RESISTOR7MM"))
    )
    (comp (ref "R70")
      (value "RESISTOR7MM")
      (footprint "eagle-import:7MM_RESISTOR")
      (libsource (lib "eagle-import") (part "RESISTOR7MM"))
    )
    (comp (ref "R71")
      (value "RESISTOR7MM")
      (footprint "eagle-import:7MM_RESISTOR")
      (libsource (lib "eagle-import") (part "RESISTOR7MM"))
    )
    (comp (ref "T1")
      (value "BC557B-PNP-TO92-EBC")
      (footprint "eagle-import:TO92-EBC")
      (libsource (lib "eagle-import") (part "-PNP-TO92-EBCBC557B"))
    )
    (comp (ref "T2")
      (value "BC547B-NPN-TO92-CBE")
      (footprint "eagle-import:TO92-CBE")
      (libsource (lib "eagle-import") (part "-NPN-TO92-CBEBC547B"))
    )
    (comp (ref "T3")
      (value "BC547B-NPN-TO92-CBE")
      (footprint "eagle-import:TO92-CBE")
      (libsource (lib "eagle-import") (part "-NPN-TO92-CBEBC547B"))
    )
    (comp (ref "T4")
      (value "BC557B-PNP-TO92-EBC")
      (footprint "eagle-import:TO92-EBC")
      (libsource (lib "eagle-import") (part "-PNP-TO92-EBCBC557B"))
    )
    (comp (ref "T5")
      (value "BC547B-NPN-TO92-CBE")
      (footprint "eagle-import:TO92-CBE")
      (libsource (lib "eagle-import") (part "-NPN-TO92-CBEBC547B"))
    )
    (comp (ref "T6")
      (value "BC547B-NPN-TO92-CBE")
      (footprint "eagle-import:TO92-CBE")
      (libsource (lib "eagle-import") (part "-NPN-TO92-CBEBC547B"))
    )
    (comp (ref "T7")
      (value "BC557B-PNP-TO92-EBC")
      (footprint "eagle-import:TO92-EBC")
      (libsource (lib "eagle-import") (part "-PNP-TO92-EBCBC557B"))
    )
    (comp (ref "T8")
      (value "BC547B-NPN-TO92-CBE")
      (footprint "eagle-import:TO92-CBE")
      (libsource (lib "eagle-import") (part "-NPN-TO92-CBEBC547B"))
    )
    (comp (ref "T9")
      (value "BC547B-NPN-TO92-CBE")
      (footprint "eagle-import:TO92-CBE")
      (libsource (lib "eagle-import") (part "-NPN-TO92-CBEBC547B"))
    )
    (comp (ref "T10")
      (value "BC557B-PNP-TO92-EBC")
      (footprint "eagle-import:TO92-EBC")
      (libsource (lib "eagle-import") (part "-PNP-TO92-EBCBC557B"))
    )
    (comp (ref "T11")
      (value "BC547B-NPN-TO92-CBE")
      (footprint "eagle-import:TO92-CBE")
      (libsource (lib "eagle-import") (part "-NPN-TO92-CBEBC547B"))
    )
    (comp (ref "T12")
      (value "BC547B-NPN-TO92-CBE")
      (footprint "eagle-import:TO92-CBE")
      (libsource (lib "eagle-import") (part "-NPN-TO92-CBEBC547B"))
    )
    (comp (ref "T13")
      (value "BC557B-PNP-TO92-EBC")
      (footprint "eagle-import:TO92-EBC")
      (libsource (lib "eagle-import") (part "-PNP-TO92-EBCBC557B"))
    )
    (comp (ref "T14")
      (value "BC547B-NPN-TO92-CBE")
      (footprint "eagle-import:TO92-CBE")
      (libsource (lib "eagle-import") (part "-NPN-TO92-CBEBC547B"))
    )
    (comp (ref "T15")
      (value "BC547B-NPN-TO92-CBE")
      (footprint "eagle-import:TO92-CBE")
      (libsource (lib "eagle-import") (part "-NPN-TO92-CBEBC547B"))
    )
    (comp (ref "T16")
      (value "BC557B-PNP-TO92-EBC")
      (footprint "eagle-import:TO92-EBC")
      (libsource (lib "eagle-import") (part "-PNP-TO92-EBCBC557B"))
    )
    (comp (ref "T17")
      (value "BC547B-NPN-TO92-CBE")
      (footprint "eagle-import:TO92-CBE")
      (libsource (lib "eagle-import") (part "-NPN-TO92-CBEBC547B"))
    )
    (comp (ref "T18")
      (value "BC547B-NPN-TO92-CBE")
      (footprint "eagle-import:TO92-CBE")
      (libsource (lib "eagle-import") (part "-NPN-TO92-CBEBC547B"))
    )
    (comp (ref "T19")
      (value "BC547B-NPN-TO92-CBE")
      (footprint "eagle-import:TO92-CBE")
      (libsource (lib "eagle-import") (part "-NPN-TO92-CBEBC547B"))
    )
    (comp (ref "T20")
      (value "BC547B-NPN-TO92-CBE")
      (footprint "eagle-import:TO92-CBE")
      (libsource (lib "eagle-import") (part "-NPN-TO92-CBEBC547B"))
    )
    (comp (ref "T21")
      (value "BC557B-PNP-TO92-EBC")
      (footprint "eagle-import:TO92-EBC")
      (libsource (lib "eagle-import") (part "-PNP-TO92-EBCBC557B"))
    )
    (comp (ref "T22")
      (value "BC547B-NPN-TO92-CBE")
      (footprint "eagle-import:TO92-CBE")
      (libsource (lib "eagle-import") (part "-NPN-TO92-CBEBC547B"))
    )
    (comp (ref "T23")
      (value "BC547B-NPN-TO92-CBE")
      (footprint "eagle-import:TO92-CBE")
      (libsource (lib "eagle-import") (part "-NPN-TO92-CBEBC547B"))
    )
    (comp (ref "T24")
      (value "BC557B-PNP-TO92-EBC")
      (footprint "eagle-import:TO92-EBC")
      (libsource (lib "eagle-import") (part "-PNP-TO92-EBCBC557B"))
    )
    (comp (ref "T25")
      (value "BC557B-PNP-TO92-EBC")
      (footprint "eagle-import:TO92-EBC")
      (libsource (lib "eagle-import") (part "-PNP-TO92-EBCBC557B"))
    )
    (comp (ref "T26")
      (value "BC557B-PNP-TO92-EBC")
      (footprint "eagle-import:TO92-EBC")
      (libsource (lib "eagle-import") (part "-PNP-TO92-EBCBC557B"))
    )
    (comp (ref "T27")
      (value "BC557B-PNP-TO92-EBC")
      (footprint "eagle-import:TO92-EBC")
      (libsource (lib "eagle-import") (part "-PNP-TO92-EBCBC557B"))
    )
    (comp (ref "T28")
      (value "BC557B-PNP-TO92-EBC")
      (footprint "eagle-import:TO92-EBC")
      (libsource (lib "eagle-import") (part "-PNP-TO92-EBCBC557B"))
    )
    (comp (ref "T29")
      (value "BC557B-PNP-TO92-EBC")
      (footprint "eagle-import:TO92-EBC")
      (libsource (lib "eagle-import") (part "-PNP-TO92-EBCBC557B"))
    )
    (comp (ref "T30")
      (value "BC547B-NPN-TO92-CBE")
      (footprint "eagle-import:TO92-CBE")
      (libsource (lib "eagle-import") (part "-NPN-TO92-CBEBC547B"))
    )
    (comp (ref "T31")
      (value "BC547B-NPN-TO92-CBE")
      (footprint "eagle-import:TO92-CBE")
      (libsource (lib "eagle-import") (part "-NPN-TO92-CBEBC547B"))
    )
    (comp (ref "T32")
      (value "BC547B-NPN-TO92-CBE")
      (footprint "eagle-import:TO92-CBE")
      (libsource (lib "eagle-import") (part "-NPN-TO92-CBEBC547B"))
    )
    (comp (ref "T33")
      (value "BC547B-NPN-TO92-CBE")
      (footprint "eagle-import:TO92-CBE")
      (libsource (lib "eagle-import") (part "-NPN-TO92-CBEBC547B"))
    )
    (comp (ref "T34")
      (value "BC547B-NPN-TO92-CBE")
      (footprint "eagle-import:TO92-CBE")
      (libsource (lib "eagle-import") (part "-NPN-TO92-CBEBC547B"))
    )
    (comp (ref "T35")
      (value "BC547B-NPN-TO92-CBE")
      (footprint "eagle-import:TO92-CBE")
      (libsource (lib "eagle-import") (part "-NPN-TO92-CBEBC547B"))
    )
  )
  (nets
    (net (code "1") (name "/BIAS") (class "Default")
      (node (ref "C8") (pin "2") (pinfunction "2_2") (pintype "passive"))
      (node (ref "R10") (pin "1") (pinfunction "1_1") (pintype "passive"))
      (node (ref "R14") (pin "1") (pinfunction "1_1") (pintype "passive"))
      (node (ref "R18") (pin "1") (pinfunction "1_1") (pintype "passive"))
      (node (ref "R2") (pin "1") (pinfunction "1_1") (pintype "passive"))
      (node (ref "R22") (pin "1") (pinfunction "1_1") (pintype "passive"))
      (node (ref "R6") (pin "1") (pinfunction "1_1") (pintype "passive"))
      (node (ref "T23") (pin "E") (pinfunction "E_E") (pintype "passive"))
    )
    (net (code "2") (name "/PWRPULSE") (class "Default")
      (node (ref "R12") (pin "2") (pinfunction "2_2") (pintype "passive"))
      (node (ref "R16") (pin "2") (pinfunction "2_2") (pintype "passive"))
      (node (ref "R20") (pin "2") (pinfunction "2_2") (pintype "passive"))
      (node (ref "R24") (pin "2") (pinfunction "2_2") (pintype "passive"))
      (node (ref "R31") (pin "1") (pinfunction "1_1") (pintype "passive"))
      (node (ref "R4") (pin "2") (pinfunction "2_2") (pintype "passive"))
      (node (ref "R8") (pin "2") (pinfunction "2_2") (pintype "passive"))
      (node (ref "T22") (pin "C") (pinfunction "C_C") (pintype "passive"))
    )
    (net (code "3") (name "GND") (class "Default")
      (node (ref "C7") (pin "1") (pinfunction "1_1") (pintype "passive"))
      (node (ref "C8") (pin "1") (pinfunction "1_1") (pintype "passive"))
      (node (ref "CN1") (pin "1") (pinfunction "1_1") (pintype "passive"))
      (node (ref "CN3") (pin "1") (pinfunction "1_1") (pintype "passive"))
      (node (ref "CN4") (pin "1") (pinfunction "1_1") (pintype "passive"))
      (node (ref "R1") (pin "1") (pinfunction "1_1") (pintype "passive"))
      (node (ref "R13") (pin "1") (pinfunction "1_1") (pintype "passive"))
      (node (ref "R17") (pin "1") (pinfunction "1_1") (pintype "passive"))
      (node (ref "R21") (pin "1") (pinfunction "1_1") (pintype "passive"))
      (node (ref "R25") (pin "1") (pinfunction "1_1") (pintype "passive"))
      (node (ref "R27") (pin "1") (pinfunction "1_1") (pintype "passive"))
      (node (ref "R29") (pin "2") (pinfunction "2_2") (pintype "passive"))
      (node (ref "R35") (pin "1") (pinfunction "1_1") (pintype "passive"))
      (node (ref "R5") (pin "1") (pinfunction "1_1") (pintype "passive"))
      (node (ref "R9") (pin "1") (pinfunction "1_1") (pintype "passive"))
      (node (ref "T11") (pin "E") (pinfunction "E_E") (pintype "passive"))
      (node (ref "T12") (pin "E") (pinfunction "E_E") (pintype "passive"))
      (node (ref "T14") (pin "E") (pinfunction "E_E") (pintype "passive"))
      (node (ref "T15") (pin "E") (pinfunction "E_E") (pintype "passive"))
      (node (ref "T17") (pin "E") (pinfunction "E_E") (pintype "passive"))
      (node (ref "T18") (pin "E") (pinfunction "E_E") (pintype "passive"))
      (node (ref "T2") (pin "E") (pinfunction "E_E") (pintype "passive"))
      (node (ref "T22") (pin "E") (pinfunction "E_E") (pintype "passive"))
      (node (ref "T3") (pin "E") (pinfunction "E_E") (pintype "passive"))
      (node (ref "T30") (pin "E") (pinfunction "E_E") (pintype "passive"))
      (node (ref "T31") (pin "E") (pinfunction "E_E") (pintype "passive"))
      (node (ref "T32") (pin "E") (pinfunction "E_E") (pintype "passive"))
      (node (ref "T33") (pin "E") (pinfunction "E_E") (pintype "passive"))
      (node (ref "T34") (pin "E") (pinfunction "E_E") (pintype "passive"))
      (node (ref "T35") (pin "E") (pinfunction "E_E") (pintype "passive"))
      (node (ref "T5") (pin "E") (pinfunction "E_E") (pintype "passive"))
      (node (ref "T6") (pin "E") (pinfunction "E_E") (pintype "passive"))
      (node (ref "T8") (pin "E") (pinfunction "E_E") (pintype "passive"))
      (node (ref "T9") (pin "E") (pinfunction "E_E") (pintype "passive"))
    )
    (net (code "4") (name "Net-(C1-Pad1)") (class "Default")
      (node (ref "C1") (pin "1") (pinfunction "1_1") (pintype "passive"))
      (node (ref "D73") (pin "A") (pinfunction "A_A") (pintype "passive"))
      (node (ref "R4") (pin "1") (pinfunction "1_1") (pintype "passive"))
    )
    (net (code "5") (name "Net-(C1-Pad2)") (class "Default")
      (node (ref "C1") (pin "2") (pinfunction "2_2") (pintype "passive"))
      (node (ref "D74") (pin "C") (pinfunction "C_C") (pintype "passive"))
      (node (ref "T4") (pin "E") (pinfunction "E_E") (pintype "passive"))
    )
    (net (code "6") (name "Net-(C2-Pad1)") (class "Default")
      (node (ref "C2") (pin "1") (pinfunction "1_1") (pintype "passive"))
      (node (ref "D74") (pin "A") (pinfunction "A_A") (pintype "passive"))
      (node (ref "R8") (pin "1") (pinfunction "1_1") (pintype "passive"))
    )
    (net (code "7") (name "Net-(C2-Pad2)") (class "Default")
      (node (ref "C2") (pin "2") (pinfunction "2_2") (pintype "passive"))
      (node (ref "D75") (pin "C") (pinfunction "C_C") (pintype "passive"))
      (node (ref "T7") (pin "E") (pinfunction "E_E") (pintype "passive"))
    )
    (net (code "8") (name "Net-(C3-Pad1)") (class "Default")
      (node (ref "C3") (pin "1") (pinfunction "1_1") (pintype "passive"))
      (node (ref "D75") (pin "A") (pinfunction "A_A") (pintype "passive"))
      (node (ref "R12") (pin "1") (pinfunction "1_1") (pintype "passive"))
    )
    (net (code "9") (name "Net-(C3-Pad2)") (class "Default")
      (node (ref "C3") (pin "2") (pinfunction "2_2") (pintype "passive"))
      (node (ref "D76") (pin "C") (pinfunction "C_C") (pintype "passive"))
      (node (ref "T10") (pin "E") (pinfunction "E_E") (pintype "passive"))
    )
    (net (code "10") (name "Net-(C4-Pad1)") (class "Default")
      (node (ref "C4") (pin "1") (pinfunction "1_1") (pintype "passive"))
      (node (ref "D76") (pin "A") (pinfunction "A_A") (pintype "passive"))
      (node (ref "R16") (pin "1") (pinfunction "1_1") (pintype "passive"))
    )
    (net (code "11") (name "Net-(C4-Pad2)") (class "Default")
      (node (ref "C4") (pin "2") (pinfunction "2_2") (pintype "passive"))
      (node (ref "D77") (pin "C") (pinfunction "C_C") (pintype "passive"))
      (node (ref "T13") (pin "E") (pinfunction "E_E") (pintype "passive"))
    )
    (net (code "12") (name "Net-(C5-Pad1)") (class "Default")
      (node (ref "C5") (pin "1") (pinfunction "1_1") (pintype "passive"))
      (node (ref "D77") (pin "A") (pinfunction "A_A") (pintype "passive"))
      (node (ref "R20") (pin "1") (pinfunction "1_1") (pintype "passive"))
    )
    (net (code "13") (name "Net-(C5-Pad2)") (class "Default")
      (node (ref "C5") (pin "2") (pinfunction "2_2") (pintype "passive"))
      (node (ref "D78") (pin "C") (pinfunction "C_C") (pintype "passive"))
      (node (ref "T16") (pin "E") (pinfunction "E_E") (pintype "passive"))
    )
    (net (code "14") (name "Net-(C6-Pad1)") (class "Default")
      (node (ref "C6") (pin "1") (pinfunction "1_1") (pintype "passive"))
      (node (ref "D78") (pin "A") (pinfunction "A_A") (pintype "passive"))
      (node (ref "R24") (pin "1") (pinfunction "1_1") (pintype "passive"))
    )
    (net (code "15") (name "Net-(C6-Pad2)") (class "Default")
      (node (ref "C6") (pin "2") (pinfunction "2_2") (pintype "passive"))
      (node (ref "D73") (pin "C") (pinfunction "C_C") (pintype "passive"))
      (node (ref "T1") (pin "E") (pinfunction "E_E") (pintype "passive"))
    )
    (net (code "16") (name "Net-(C7-Pad2)") (class "Default")
      (node (ref "C7") (pin "2") (pinfunction "2_2") (pintype "passive"))
      (node (ref "D79") (pin "C") (pinfunction "C_C") (pintype "passive"))
      (node (ref "R32") (pin "2") (pinfunction "2_2") (pintype "passive"))
      (node (ref "T19") (pin "B") (pinfunction "B_B") (pintype "passive"))
    )
    (net (code "17") (name "Net-(CN2-Pad1)") (class "Default")
      (node (ref "CN2") (pin "1") (pinfunction "1_1") (pintype "passive"))
      (node (ref "D49") (pin "C") (pinfunction "C_C") (pintype "passive"))
      (node (ref "D50") (pin "C") (pinfunction "C_C") (pintype "passive"))
      (node (ref "D51") (pin "C") (pinfunction "C_C") (pintype "passive"))
      (node (ref "D52") (pin "C") (pinfunction "C_C") (pintype "passive"))
      (node (ref "D53") (pin "C") (pinfunction "C_C") (pintype "passive"))
      (node (ref "D54") (pin "C") (pinfunction "C_C") (pintype "passive"))
    )
    (net (code "18") (name "Net-(CN2-Pad2)") (class "Default")
      (node (ref "CN2") (pin "2") (pinfunction "2_2") (pintype "passive"))
      (node (ref "D55") (pin "C") (pinfunction "C_C") (pintype "passive"))
      (node (ref "D56") (pin "C") (pinfunction "C_C") (pintype "passive"))
      (node (ref "D57") (pin "C") (pinfunction "C_C") (pintype "passive"))
      (node (ref "D58") (pin "C") (pinfunction "C_C") (pintype "passive"))
      (node (ref "D59") (pin "C") (pinfunction "C_C") (pintype "passive"))
      (node (ref "D60") (pin "C") (pinfunction "C_C") (pintype "passive"))
    )
    (net (code "19") (name "Net-(CN2-Pad3)") (class "Default")
      (node (ref "CN2") (pin "3") (pinfunction "3_3") (pintype "passive"))
      (node (ref "D61") (pin "C") (pinfunction "C_C") (pintype "passive"))
      (node (ref "D62") (pin "C") (pinfunction "C_C") (pintype "passive"))
      (node (ref "D63") (pin "C") (pinfunction "C_C") (pintype "passive"))
      (node (ref "D64") (pin "C") (pinfunction "C_C") (pintype "passive"))
      (node (ref "D65") (pin "C") (pinfunction "C_C") (pintype "passive"))
      (node (ref "D66") (pin "C") (pinfunction "C_C") (pintype "passive"))
    )
    (net (code "20") (name "Net-(CN2-Pad4)") (class "Default")
      (node (ref "CN2") (pin "4") (pinfunction "4_4") (pintype "passive"))
      (node (ref "D67") (pin "C") (pinfunction "C_C") (pintype "passive"))
      (node (ref "D68") (pin "C") (pinfunction "C_C") (pintype "passive"))
      (node (ref "D69") (pin "C") (pinfunction "C_C") (pintype "passive"))
      (node (ref "D70") (pin "C") (pinfunction "C_C") (pintype "passive"))
      (node (ref "D71") (pin "C") (pinfunction "C_C") (pintype "passive"))
      (node (ref "D72") (pin "C") (pinfunction "C_C") (pintype "passive"))
    )
    (net (code "21") (name "Net-(D1-PadA)") (class "Default")
      (node (ref "D1") (pin "A") (pinfunction "A_A") (pintype "passive"))
      (node (ref "D25") (pin "A") (pinfunction "A_A") (pintype "passive"))
      (node (ref "D49") (pin "A") (pinfunction "A_A") (pintype "passive"))
      (node (ref "R48") (pin "2") (pinfunction "2_2") (pintype "passive"))
    )
    (net (code "22") (name "Net-(D1-PadC)") (class "Default")
      (node (ref "D1") (pin "C") (pinfunction "C_C") (pintype "passive"))
      (node (ref "J1A") (pin "1") (pinfunction "1_1") (pintype "passive"))
    )
    (net (code "23") (name "Net-(D2-PadA)") (class "Default")
      (node (ref "D2") (pin "A") (pinfunction "A_A") (pintype "passive"))
      (node (ref "D26") (pin "A") (pinfunction "A_A") (pintype "passive"))
      (node (ref "D55") (pin "A") (pinfunction "A_A") (pintype "passive"))
      (node (ref "R49") (pin "2") (pinfunction "2_2") (pintype "passive"))
    )
    (net (code "24") (name "Net-(D2-PadC)") (class "Default")
      (node (ref "D2") (pin "C") (pinfunction "C_C") (pintype "passive"))
      (node (ref "J1A") (pin "2") (pinfunction "2_2") (pintype "passive"))
    )
    (net (code "25") (name "Net-(D3-PadC)") (class "Default")
      (node (ref "D3") (pin "C") (pinfunction "C_C") (pintype "passive"))
      (node (ref "J1A") (pin "3") (pinfunction "3_3") (pintype "passive"))
    )
    (net (code "26") (name "Net-(D4-PadC)") (class "Default")
      (node (ref "D4") (pin "C") (pinfunction "C_C") (pintype "passive"))
      (node (ref "J1A") (pin "4") (pinfunction "4_4") (pintype "passive"))
    )
    (net (code "27") (name "Net-(D5-PadC)") (class "Default")
      (node (ref "D5") (pin "C") (pinfunction "C_C") (pintype "passive"))
      (node (ref "J1A") (pin "5") (pinfunction "5_5") (pintype "passive"))
    )
    (net (code "28") (name "Net-(D6-PadC)") (class "Default")
      (node (ref "D6") (pin "C") (pinfunction "C_C") (pintype "passive"))
      (node (ref "J1A") (pin "6") (pinfunction "6_6") (pintype "passive"))
    )
    (net (code "29") (name "Net-(D7-PadC)") (class "Default")
      (node (ref "D7") (pin "C") (pinfunction "C_C") (pintype "passive"))
      (node (ref "J1A") (pin "7") (pinfunction "7_7") (pintype "passive"))
    )
    (net (code "30") (name "Net-(D8-PadC)") (class "Default")
      (node (ref "D8") (pin "C") (pinfunction "C_C") (pintype "passive"))
      (node (ref "J1A") (pin "8") (pinfunction "8_8") (pintype "passive"))
    )
    (net (code "31") (name "Net-(D9-PadC)") (class "Default")
      (node (ref "D9") (pin "C") (pinfunction "C_C") (pintype "passive"))
      (node (ref "J1B") (pin "1") (pinfunction "1_1") (pintype "passive"))
    )
    (net (code "32") (name "Net-(D10-PadA)") (class "Default")
      (node (ref "D10") (pin "A") (pinfunction "A_A") (pintype "passive"))
      (node (ref "D34") (pin "A") (pinfunction "A_A") (pintype "passive"))
      (node (ref "D57") (pin "A") (pinfunction "A_A") (pintype "passive"))
      (node (ref "R57") (pin "2") (pinfunction "2_2") (pintype "passive"))
    )
    (net (code "33") (name "Net-(D10-PadC)") (class "Default")
      (node (ref "D10") (pin "C") (pinfunction "C_C") (pintype "passive"))
      (node (ref "J1B") (pin "2") (pinfunction "2_2") (pintype "passive"))
    )
    (net (code "34") (name "Net-(D11-PadA)") (class "Default")
      (node (ref "D11") (pin "A") (pinfunction "A_A") (pintype "passive"))
      (node (ref "D35") (pin "A") (pinfunction "A_A") (pintype "passive"))
      (node (ref "D63") (pin "A") (pinfunction "A_A") (pintype "passive"))
      (node (ref "R58") (pin "2") (pinfunction "2_2") (pintype "passive"))
    )
    (net (code "35") (name "Net-(D11-PadC)") (class "Default")
      (node (ref "D11") (pin "C") (pinfunction "C_C") (pintype "passive"))
      (node (ref "J1B") (pin "3") (pinfunction "3_3") (pintype "passive"))
    )
    (net (code "36") (name "Net-(D12-PadA)") (class "Default")
      (node (ref "D12") (pin "A") (pinfunction "A_A") (pintype "passive"))
      (node (ref "D36") (pin "A") (pinfunction "A_A") (pintype "passive"))
      (node (ref "D69") (pin "A") (pinfunction "A_A") (pintype "passive"))
      (node (ref "R59") (pin "2") (pinfunction "2_2") (pintype "passive"))
    )
    (net (code "37") (name "Net-(D12-PadC)") (class "Default")
      (node (ref "D12") (pin "C") (pinfunction "C_C") (pintype "passive"))
      (node (ref "J1B") (pin "4") (pinfunction "4_4") (pintype "passive"))
    )
    (net (code "38") (name "Net-(D13-PadA)") (class "Default")
      (node (ref "D13") (pin "A") (pinfunction "A_A") (pintype "passive"))
      (node (ref "D37") (pin "A") (pinfunction "A_A") (pintype "passive"))
      (node (ref "D52") (pin "A") (pinfunction "A_A") (pintype "passive"))
      (node (ref "R60") (pin "2") (pinfunction "2_2") (pintype "passive"))
    )
    (net (code "39") (name "Net-(D13-PadC)") (class "Default")
      (node (ref "D13") (pin "C") (pinfunction "C_C") (pintype "passive"))
      (node (ref "J1B") (pin "5") (pinfunction "5_5") (pintype "passive"))
    )
    (net (code "40") (name "Net-(D14-PadA)") (class "Default")
      (node (ref "D14") (pin "A") (pinfunction "A_A") (pintype "passive"))
      (node (ref "D38") (pin "A") (pinfunction "A_A") (pintype "passive"))
      (node (ref "D58") (pin "A") (pinfunction "A_A") (pintype "passive"))
      (node (ref "R61") (pin "2") (pinfunction "2_2") (pintype "passive"))
    )
    (net (code "41") (name "Net-(D14-PadC)") (class "Default")
      (node (ref "D14") (pin "C") (pinfunction "C_C") (pintype "passive"))
      (node (ref "J1B") (pin "6") (pinfunction "6_6") (pintype "passive"))
    )
    (net (code "42") (name "Net-(D15-PadA)") (class "Default")
      (node (ref "D15") (pin "A") (pinfunction "A_A") (pintype "passive"))
      (node (ref "D39") (pin "A") (pinfunction "A_A") (pintype "passive"))
      (node (ref "D64") (pin "A") (pinfunction "A_A") (pintype "passive"))
      (node (ref "R62") (pin "2") (pinfunction "2_2") (pintype "passive"))
    )
    (net (code "43") (name "Net-(D15-PadC)") (class "Default")
      (node (ref "D15") (pin "C") (pinfunction "C_C") (pintype "passive"))
      (node (ref "J1B") (pin "7") (pinfunction "7_7") (pintype "passive"))
    )
    (net (code "44") (name "Net-(D16-PadA)") (class "Default")
      (node (ref "D16") (pin "A") (pinfunction "A_A") (pintype "passive"))
      (node (ref "D40") (pin "A") (pinfunction "A_A") (pintype "passive"))
      (node (ref "D70") (pin "A") (pinfunction "A_A") (pintype "passive"))
      (node (ref "R63") (pin "2") (pinfunction "2_2") (pintype "passive"))
    )
    (net (code "45") (name "Net-(D16-PadC)") (class "Default")
      (node (ref "D16") (pin "C") (pinfunction "C_C") (pintype "passive"))
      (node (ref "J1B") (pin "8") (pinfunction "8_8") (pintype "passive"))
    )
    (net (code "46") (name "Net-(D17-PadA)") (class "Default")
      (node (ref "D17") (pin "A") (pinfunction "A_A") (pintype "passive"))
      (node (ref "D41") (pin "A") (pinfunction "A_A") (pintype "passive"))
      (node (ref "D53") (pin "A") (pinfunction "A_A") (pintype "passive"))
      (node (ref "R64") (pin "2") (pinfunction "2_2") (pintype "passive"))
    )
    (net (code "47") (name "Net-(D17-PadC)") (class "Default")
      (node (ref "D17") (pin "C") (pinfunction "C_C") (pintype "passive"))
      (node (ref "J1C") (pin "1") (pinfunction "1_1") (pintype "passive"))
    )
    (net (code "48") (name "Net-(D18-PadA)") (class "Default")
      (node (ref "D18") (pin "A") (pinfunction "A_A") (pintype "passive"))
      (node (ref "D42") (pin "A") (pinfunction "A_A") (pintype "passive"))
      (node (ref "D59") (pin "A") (pinfunction "A_A") (pintype "passive"))
      (node (ref "R65") (pin "2") (pinfunction "2_2") (pintype "passive"))
    )
    (net (code "49") (name "Net-(D18-PadC)") (class "Default")
      (node (ref "D18") (pin "C") (pinfunction "C_C") (pintype "passive"))
      (node (ref "J1C") (pin "2") (pinfunction "2_2") (pintype "passive"))
    )
    (net (code "50") (name "Net-(D19-PadA)") (class "Default")
      (node (ref "D19") (pin "A") (pinfunction "A_A") (pintype "passive"))
      (node (ref "D43") (pin "A") (pinfunction "A_A") (pintype "passive"))
      (node (ref "D65") (pin "A") (pinfunction "A_A") (pintype "passive"))
      (node (ref "R66") (pin "2") (pinfunction "2_2") (pintype "passive"))
    )
    (net (code "51") (name "Net-(D19-PadC)") (class "Default")
      (node (ref "D19") (pin "C") (pinfunction "C_C") (pintype "passive"))
      (node (ref "J1C") (pin "3") (pinfunction "3_3") (pintype "passive"))
    )
    (net (code "52") (name "Net-(D20-PadA)") (class "Default")
      (node (ref "D20") (pin "A") (pinfunction "A_A") (pintype "passive"))
      (node (ref "D44") (pin "A") (pinfunction "A_A") (pintype "passive"))
      (node (ref "D71") (pin "A") (pinfunction "A_A") (pintype "passive"))
      (node (ref "R67") (pin "2") (pinfunction "2_2") (pintype "passive"))
    )
    (net (code "53") (name "Net-(D20-PadC)") (class "Default")
      (node (ref "D20") (pin "C") (pinfunction "C_C") (pintype "passive"))
      (node (ref "J1C") (pin "4") (pinfunction "4_4") (pintype "passive"))
    )
    (net (code "54") (name "Net-(D21-PadA)") (class "Default")
      (node (ref "D21") (pin "A") (pinfunction "A_A") (pintype "passive"))
      (node (ref "D45") (pin "A") (pinfunction "A_A") (pintype "passive"))
      (node (ref "D54") (pin "A") (pinfunction "A_A") (pintype "passive"))
      (node (ref "R68") (pin "2") (pinfunction "2_2") (pintype "passive"))
    )
    (net (code "55") (name "Net-(D21-PadC)") (class "Default")
      (node (ref "D21") (pin "C") (pinfunction "C_C") (pintype "passive"))
      (node (ref "J1C") (pin "5") (pinfunction "5_5") (pintype "passive"))
    )
    (net (code "56") (name "Net-(D22-PadA)") (class "Default")
      (node (ref "D22") (pin "A") (pinfunction "A_A") (pintype "passive"))
      (node (ref "D46") (pin "A") (pinfunction "A_A") (pintype "passive"))
      (node (ref "D60") (pin "A") (pinfunction "A_A") (pintype "passive"))
      (node (ref "R69") (pin "2") (pinfunction "2_2") (pintype "passive"))
    )
    (net (code "57") (name "Net-(D22-PadC)") (class "Default")
      (node (ref "D22") (pin "C") (pinfunction "C_C") (pintype "passive"))
      (node (ref "J1C") (pin "6") (pinfunction "6_6") (pintype "passive"))
    )
    (net (code "58") (name "Net-(D23-PadA)") (class "Default")
      (node (ref "D23") (pin "A") (pinfunction "A_A") (pintype "passive"))
      (node (ref "D47") (pin "A") (pinfunction "A_A") (pintype "passive"))
      (node (ref "D66") (pin "A") (pinfunction "A_A") (pintype "passive"))
      (node (ref "R70") (pin "2") (pinfunction "2_2") (pintype "passive"))
    )
    (net (code "59") (name "Net-(D23-PadC)") (class "Default")
      (node (ref "D23") (pin "C") (pinfunction "C_C") (pintype "passive"))
      (node (ref "J1C") (pin "7") (pinfunction "7_7") (pintype "passive"))
    )
    (net (code "60") (name "Net-(D24-PadA)") (class "Default")
      (node (ref "D24") (pin "A") (pinfunction "A_A") (pintype "passive"))
      (node (ref "D48") (pin "A") (pinfunction "A_A") (pintype "passive"))
      (node (ref "D72") (pin "A") (pinfunction "A_A") (pintype "passive"))
      (node (ref "R71") (pin "2") (pinfunction "2_2") (pintype "passive"))
    )
    (net (code "61") (name "Net-(D24-PadC)") (class "Default")
      (node (ref "D24") (pin "C") (pinfunction "C_C") (pintype "passive"))
      (node (ref "J1C") (pin "8") (pinfunction "8_8") (pintype "passive"))
    )
    (net (code "62") (name "Net-(D25-PadC)") (class "Default")
      (node (ref "D25") (pin "C") (pinfunction "C_C") (pintype "passive"))
      (node (ref "D26") (pin "C") (pinfunction "C_C") (pintype "passive"))
      (node (ref "D27") (pin "C") (pinfunction "C_C") (pintype "passive"))
      (node (ref "D28") (pin "C") (pinfunction "C_C") (pintype "passive"))
      (node (ref "R47") (pin "1") (pinfunction "1_1") (pintype "passive"))
      (node (ref "T3") (pin "C") (pinfunction "C_C") (pintype "passive"))
    )
    (net (code "63") (name "Net-(D27-PadA)") (class "Default")
      (node (ref "D27") (pin "A") (pinfunction "A_A") (pintype "passive"))
      (node (ref "D3") (pin "A") (pinfunction "A_A") (pintype "passive"))
      (node (ref "D61") (pin "A") (pinfunction "A_A") (pintype "passive"))
      (node (ref "R50") (pin "2") (pinfunction "2_2") (pintype "passive"))
    )
    (net (code "64") (name "Net-(D28-PadA)") (class "Default")
      (node (ref "D28") (pin "A") (pinfunction "A_A") (pintype "passive"))
      (node (ref "D4") (pin "A") (pinfunction "A_A") (pintype "passive"))
      (node (ref "D67") (pin "A") (pinfunction "A_A") (pintype "passive"))
      (node (ref "R51") (pin "2") (pinfunction "2_2") (pintype "passive"))
    )
    (net (code "65") (name "Net-(D29-PadA)") (class "Default")
      (node (ref "D29") (pin "A") (pinfunction "A_A") (pintype "passive"))
      (node (ref "D5") (pin "A") (pinfunction "A_A") (pintype "passive"))
      (node (ref "D50") (pin "A") (pinfunction "A_A") (pintype "passive"))
      (node (ref "R52") (pin "2") (pinfunction "2_2") (pintype "passive"))
    )
    (net (code "66") (name "Net-(D29-PadC)") (class "Default")
      (node (ref "D29") (pin "C") (pinfunction "C_C") (pintype "passive"))
      (node (ref "D30") (pin "C") (pinfunction "C_C") (pintype "passive"))
      (node (ref "D31") (pin "C") (pinfunction "C_C") (pintype "passive"))
      (node (ref "D32") (pin "C") (pinfunction "C_C") (pintype "passive"))
      (node (ref "R46") (pin "1") (pinfunction "1_1") (pintype "passive"))
      (node (ref "T6") (pin "C") (pinfunction "C_C") (pintype "passive"))
    )
    (net (code "67") (name "Net-(D30-PadA)") (class "Default")
      (node (ref "D30") (pin "A") (pinfunction "A_A") (pintype "passive"))
      (node (ref "D56") (pin "A") (pinfunction "A_A") (pintype "passive"))
      (node (ref "D6") (pin "A") (pinfunction "A_A") (pintype "passive"))
      (node (ref "R53") (pin "2") (pinfunction "2_2") (pintype "passive"))
    )
    (net (code "68") (name "Net-(D31-PadA)") (class "Default")
      (node (ref "D31") (pin "A") (pinfunction "A_A") (pintype "passive"))
      (node (ref "D62") (pin "A") (pinfunction "A_A") (pintype "passive"))
      (node (ref "D7") (pin "A") (pinfunction "A_A") (pintype "passive"))
      (node (ref "R54") (pin "2") (pinfunction "2_2") (pintype "passive"))
    )
    (net (code "69") (name "Net-(D32-PadA)") (class "Default")
      (node (ref "D32") (pin "A") (pinfunction "A_A") (pintype "passive"))
      (node (ref "D68") (pin "A") (pinfunction "A_A") (pintype "passive"))
      (node (ref "D8") (pin "A") (pinfunction "A_A") (pintype "passive"))
      (node (ref "R55") (pin "2") (pinfunction "2_2") (pintype "passive"))
    )
    (net (code "70") (name "Net-(D33-PadA)") (class "Default")
      (node (ref "D33") (pin "A") (pinfunction "A_A") (pintype "passive"))
      (node (ref "D51") (pin "A") (pinfunction "A_A") (pintype "passive"))
      (node (ref "D9") (pin "A") (pinfunction "A_A") (pintype "passive"))
      (node (ref "R56") (pin "2") (pinfunction "2_2") (pintype "passive"))
    )
    (net (code "71") (name "Net-(D33-PadC)") (class "Default")
      (node (ref "D33") (pin "C") (pinfunction "C_C") (pintype "passive"))
      (node (ref "D34") (pin "C") (pinfunction "C_C") (pintype "passive"))
      (node (ref "D35") (pin "C") (pinfunction "C_C") (pintype "passive"))
      (node (ref "D36") (pin "C") (pinfunction "C_C") (pintype "passive"))
      (node (ref "R45") (pin "1") (pinfunction "1_1") (pintype "passive"))
      (node (ref "T9") (pin "C") (pinfunction "C_C") (pintype "passive"))
    )
    (net (code "72") (name "Net-(D37-PadC)") (class "Default")
      (node (ref "D37") (pin "C") (pinfunction "C_C") (pintype "passive"))
      (node (ref "D38") (pin "C") (pinfunction "C_C") (pintype "passive"))
      (node (ref "D39") (pin "C") (pinfunction "C_C") (pintype "passive"))
      (node (ref "D40") (pin "C") (pinfunction "C_C") (pintype "passive"))
      (node (ref "R44") (pin "1") (pinfunction "1_1") (pintype "passive"))
      (node (ref "T12") (pin "C") (pinfunction "C_C") (pintype "passive"))
    )
    (net (code "73") (name "Net-(D41-PadC)") (class "Default")
      (node (ref "D41") (pin "C") (pinfunction "C_C") (pintype "passive"))
      (node (ref "D42") (pin "C") (pinfunction "C_C") (pintype "passive"))
      (node (ref "D43") (pin "C") (pinfunction "C_C") (pintype "passive"))
      (node (ref "D44") (pin "C") (pinfunction "C_C") (pintype "passive"))
      (node (ref "R43") (pin "1") (pinfunction "1_1") (pintype "passive"))
      (node (ref "T15") (pin "C") (pinfunction "C_C") (pintype "passive"))
    )
    (net (code "74") (name "Net-(D45-PadC)") (class "Default")
      (node (ref "D45") (pin "C") (pinfunction "C_C") (pintype "passive"))
      (node (ref "D46") (pin "C") (pinfunction "C_C") (pintype "passive"))
      (node (ref "D47") (pin "C") (pinfunction "C_C") (pintype "passive"))
      (node (ref "D48") (pin "C") (pinfunction "C_C") (pintype "passive"))
      (node (ref "R42") (pin "1") (pinfunction "1_1") (pintype "passive"))
      (node (ref "T18") (pin "C") (pinfunction "C_C") (pintype "passive"))
    )
    (net (code "75") (name "Net-(D79-PadA)") (class "Default")
      (node (ref "D79") (pin "A") (pinfunction "A_A") (pintype "passive"))
      (node (ref "R33") (pin "2") (pinfunction "2_2") (pintype "passive"))
    )
    (net (code "76") (name "Net-(J1-Pad1)") (class "Default")
      (node (ref "J1") (pin "1") (pinfunction "1_1") (pintype "passive"))
      (node (ref "T29") (pin "C") (pinfunction "C_C") (pintype "passive"))
    )
    (net (code "77") (name "Net-(J1-Pad2)") (class "Default")
      (node (ref "J1") (pin "2") (pinfunction "2_2") (pintype "passive"))
      (node (ref "T28") (pin "C") (pinfunction "C_C") (pintype "passive"))
    )
    (net (code "78") (name "Net-(J1-Pad3)") (class "Default")
      (node (ref "J1") (pin "3") (pinfunction "3_3") (pintype "passive"))
      (node (ref "T27") (pin "C") (pinfunction "C_C") (pintype "passive"))
    )
    (net (code "79") (name "Net-(J1-Pad4)") (class "Default")
      (node (ref "J1") (pin "4") (pinfunction "4_4") (pintype "passive"))
      (node (ref "T26") (pin "C") (pinfunction "C_C") (pintype "passive"))
    )
    (net (code "80") (name "Net-(J1-Pad5)") (class "Default")
      (node (ref "J1") (pin "5") (pinfunction "5_5") (pintype "passive"))
      (node (ref "T25") (pin "C") (pinfunction "C_C") (pintype "passive"))
    )
    (net (code "81") (name "Net-(J1-Pad6)") (class "Default")
      (node (ref "J1") (pin "6") (pinfunction "6_6") (pintype "passive"))
      (node (ref "T24") (pin "C") (pinfunction "C_C") (pintype "passive"))
    )
    (net (code "82") (name "Net-(R1-Pad2)") (class "Default")
      (node (ref "R1") (pin "2") (pinfunction "2_2") (pintype "passive"))
      (node (ref "T1") (pin "C") (pinfunction "C_C") (pintype "passive"))
      (node (ref "T2") (pin "B") (pinfunction "B_B") (pintype "passive"))
    )
    (net (code "83") (name "Net-(R2-Pad2)") (class "Default")
      (node (ref "R2") (pin "2") (pinfunction "2_2") (pintype "passive"))
      (node (ref "R3") (pin "2") (pinfunction "2_2") (pintype "passive"))
      (node (ref "T1") (pin "B") (pinfunction "B_B") (pintype "passive"))
      (node (ref "T2") (pin "C") (pinfunction "C_C") (pintype "passive"))
    )
    (net (code "84") (name "Net-(R3-Pad1)") (class "Default")
      (node (ref "R3") (pin "1") (pinfunction "1_1") (pintype "passive"))
      (node (ref "T3") (pin "B") (pinfunction "B_B") (pintype "passive"))
    )
    (net (code "85") (name "Net-(R5-Pad2)") (class "Default")
      (node (ref "R5") (pin "2") (pinfunction "2_2") (pintype "passive"))
      (node (ref "T4") (pin "C") (pinfunction "C_C") (pintype "passive"))
      (node (ref "T5") (pin "B") (pinfunction "B_B") (pintype "passive"))
    )
    (net (code "86") (name "Net-(R6-Pad2)") (class "Default")
      (node (ref "R6") (pin "2") (pinfunction "2_2") (pintype "passive"))
      (node (ref "R7") (pin "2") (pinfunction "2_2") (pintype "passive"))
      (node (ref "T4") (pin "B") (pinfunction "B_B") (pintype "passive"))
      (node (ref "T5") (pin "C") (pinfunction "C_C") (pintype "passive"))
    )
    (net (code "87") (name "Net-(R7-Pad1)") (class "Default")
      (node (ref "R7") (pin "1") (pinfunction "1_1") (pintype "passive"))
      (node (ref "T6") (pin "B") (pinfunction "B_B") (pintype "passive"))
    )
    (net (code "88") (name "Net-(R9-Pad2)") (class "Default")
      (node (ref "R9") (pin "2") (pinfunction "2_2") (pintype "passive"))
      (node (ref "T7") (pin "C") (pinfunction "C_C") (pintype "passive"))
      (node (ref "T8") (pin "B") (pinfunction "B_B") (pintype "passive"))
    )
    (net (code "89") (name "Net-(R10-Pad2)") (class "Default")
      (node (ref "R10") (pin "2") (pinfunction "2_2") (pintype "passive"))
      (node (ref "R11") (pin "2") (pinfunction "2_2") (pintype "passive"))
      (node (ref "T7") (pin "B") (pinfunction "B_B") (pintype "passive"))
      (node (ref "T8") (pin "C") (pinfunction "C_C") (pintype "passive"))
    )
    (net (code "90") (name "Net-(R11-Pad1)") (class "Default")
      (node (ref "R11") (pin "1") (pinfunction "1_1") (pintype "passive"))
      (node (ref "T9") (pin "B") (pinfunction "B_B") (pintype "passive"))
    )
    (net (code "91") (name "Net-(R13-Pad2)") (class "Default")
      (node (ref "R13") (pin "2") (pinfunction "2_2") (pintype "passive"))
      (node (ref "T10") (pin "C") (pinfunction "C_C") (pintype "passive"))
      (node (ref "T11") (pin "B") (pinfunction "B_B") (pintype "passive"))
    )
    (net (code "92") (name "Net-(R14-Pad2)") (class "Default")
      (node (ref "R14") (pin "2") (pinfunction "2_2") (pintype "passive"))
      (node (ref "R15") (pin "2") (pinfunction "2_2") (pintype "passive"))
      (node (ref "T10") (pin "B") (pinfunction "B_B") (pintype "passive"))
      (node (ref "T11") (pin "C") (pinfunction "C_C") (pintype "passive"))
    )
    (net (code "93") (name "Net-(R15-Pad1)") (class "Default")
      (node (ref "R15") (pin "1") (pinfunction "1_1") (pintype "passive"))
      (node (ref "T12") (pin "B") (pinfunction "B_B") (pintype "passive"))
    )
    (net (code "94") (name "Net-(R17-Pad2)") (class "Default")
      (node (ref "R17") (pin "2") (pinfunction "2_2") (pintype "passive"))
      (node (ref "T13") (pin "C") (pinfunction "C_C") (pintype "passive"))
      (node (ref "T14") (pin "B") (pinfunction "B_B") (pintype "passive"))
    )
    (net (code "95") (name "Net-(R18-Pad2)") (class "Default")
      (node (ref "R18") (pin "2") (pinfunction "2_2") (pintype "passive"))
      (node (ref "R19") (pin "2") (pinfunction "2_2") (pintype "passive"))
      (node (ref "T13") (pin "B") (pinfunction "B_B") (pintype "passive"))
      (node (ref "T14") (pin "C") (pinfunction "C_C") (pintype "passive"))
    )
    (net (code "96") (name "Net-(R19-Pad1)") (class "Default")
      (node (ref "R19") (pin "1") (pinfunction "1_1") (pintype "passive"))
      (node (ref "T15") (pin "B") (pinfunction "B_B") (pintype "passive"))
    )
    (net (code "97") (name "Net-(R21-Pad2)") (class "Default")
      (node (ref "R21") (pin "2") (pinfunction "2_2") (pintype "passive"))
      (node (ref "T16") (pin "C") (pinfunction "C_C") (pintype "passive"))
      (node (ref "T17") (pin "B") (pinfunction "B_B") (pintype "passive"))
    )
    (net (code "98") (name "Net-(R22-Pad2)") (class "Default")
      (node (ref "R22") (pin "2") (pinfunction "2_2") (pintype "passive"))
      (node (ref "R23") (pin "2") (pinfunction "2_2") (pintype "passive"))
      (node (ref "T16") (pin "B") (pinfunction "B_B") (pintype "passive"))
      (node (ref "T17") (pin "C") (pinfunction "C_C") (pintype "passive"))
    )
    (net (code "99") (name "Net-(R23-Pad1)") (class "Default")
      (node (ref "R23") (pin "1") (pinfunction "1_1") (pintype "passive"))
      (node (ref "T18") (pin "B") (pinfunction "B_B") (pintype "passive"))
    )
    (net (code "100") (name "Net-(R25-Pad2)") (class "Default")
      (node (ref "R25") (pin "2") (pinfunction "2_2") (pintype "passive"))
      (node (ref "T19") (pin "E") (pinfunction "E_E") (pintype "passive"))
      (node (ref "T20") (pin "E") (pinfunction "E_E") (pintype "passive"))
    )
    (net (code "101") (name "Net-(R26-Pad1)") (class "Default")
      (node (ref "R26") (pin "1") (pinfunction "1_1") (pintype "passive"))
      (node (ref "R27") (pin "2") (pinfunction "2_2") (pintype "passive"))
      (node (ref "R28") (pin "2") (pinfunction "2_2") (pintype "passive"))
      (node (ref "T20") (pin "B") (pinfunction "B_B") (pintype "passive"))
    )
    (net (code "102") (name "Net-(R28-Pad1)") (class "Default")
      (node (ref "R28") (pin "1") (pinfunction "1_1") (pintype "passive"))
      (node (ref "R29") (pin "1") (pinfunction "1_1") (pintype "passive"))
      (node (ref "R30") (pin "2") (pinfunction "2_2") (pintype "passive"))
      (node (ref "R32") (pin "1") (pinfunction "1_1") (pintype "passive"))
      (node (ref "R33") (pin "1") (pinfunction "1_1") (pintype "passive"))
      (node (ref "T21") (pin "C") (pinfunction "C_C") (pintype "passive"))
    )
    (net (code "103") (name "Net-(R30-Pad1)") (class "Default")
      (node (ref "R30") (pin "1") (pinfunction "1_1") (pintype "passive"))
      (node (ref "T22") (pin "B") (pinfunction "B_B") (pintype "passive"))
    )
    (net (code "104") (name "Net-(R34-Pad1)") (class "Default")
      (node (ref "R34") (pin "1") (pinfunction "1_1") (pintype "passive"))
      (node (ref "R35") (pin "2") (pinfunction "2_2") (pintype "passive"))
      (node (ref "T23") (pin "B") (pinfunction "B_B") (pintype "passive"))
    )
    (net (code "105") (name "Net-(R36-Pad1)") (class "Default")
      (node (ref "R36") (pin "1") (pinfunction "1_1") (pintype "passive"))
      (node (ref "T30") (pin "C") (pinfunction "C_C") (pintype "passive"))
    )
    (net (code "106") (name "Net-(R36-Pad2)") (class "Default")
      (node (ref "R36") (pin "2") (pinfunction "2_2") (pintype "passive"))
      (node (ref "T24") (pin "B") (pinfunction "B_B") (pintype "passive"))
    )
    (net (code "107") (name "Net-(R37-Pad1)") (class "Default")
      (node (ref "R37") (pin "1") (pinfunction "1_1") (pintype "passive"))
      (node (ref "T31") (pin "C") (pinfunction "C_C") (pintype "passive"))
    )
    (net (code "108") (name "Net-(R37-Pad2)") (class "Default")
      (node (ref "R37") (pin "2") (pinfunction "2_2") (pintype "passive"))
      (node (ref "T25") (pin "B") (pinfunction "B_B") (pintype "passive"))
    )
    (net (code "109") (name "Net-(R38-Pad1)") (class "Default")
      (node (ref "R38") (pin "1") (pinfunction "1_1") (pintype "passive"))
      (node (ref "T32") (pin "C") (pinfunction "C_C") (pintype "passive"))
    )
    (net (code "110") (name "Net-(R38-Pad2)") (class "Default")
      (node (ref "R38") (pin "2") (pinfunction "2_2") (pintype "passive"))
      (node (ref "T26") (pin "B") (pinfunction "B_B") (pintype "passive"))
    )
    (net (code "111") (name "Net-(R39-Pad1)") (class "Default")
      (node (ref "R39") (pin "1") (pinfunction "1_1") (pintype "passive"))
      (node (ref "T33") (pin "C") (pinfunction "C_C") (pintype "passive"))
    )
    (net (code "112") (name "Net-(R39-Pad2)") (class "Default")
      (node (ref "R39") (pin "2") (pinfunction "2_2") (pintype "passive"))
      (node (ref "T27") (pin "B") (pinfunction "B_B") (pintype "passive"))
    )
    (net (code "113") (name "Net-(R40-Pad1)") (class "Default")
      (node (ref "R40") (pin "1") (pinfunction "1_1") (pintype "passive"))
      (node (ref "T34") (pin "C") (pinfunction "C_C") (pintype "passive"))
    )
    (net (code "114") (name "Net-(R40-Pad2)") (class "Default")
      (node (ref "R40") (pin "2") (pinfunction "2_2") (pintype "passive"))
      (node (ref "T28") (pin "B") (pinfunction "B_B") (pintype "passive"))
    )
    (net (code "115") (name "Net-(R41-Pad1)") (class "Default")
      (node (ref "R41") (pin "1") (pinfunction "1_1") (pintype "passive"))
      (node (ref "T35") (pin "C") (pinfunction "C_C") (pintype "passive"))
    )
    (net (code "116") (name "Net-(R41-Pad2)") (class "Default")
      (node (ref "R41") (pin "2") (pinfunction "2_2") (pintype "passive"))
      (node (ref "T29") (pin "B") (pinfunction "B_B") (pintype "passive"))
    )
    (net (code "117") (name "Net-(R42-Pad2)") (class "Default")
      (node (ref "R42") (pin "2") (pinfunction "2_2") (pintype "passive"))
      (node (ref "T30") (pin "B") (pinfunction "B_B") (pintype "passive"))
    )
    (net (code "118") (name "Net-(R43-Pad2)") (class "Default")
      (node (ref "R43") (pin "2") (pinfunction "2_2") (pintype "passive"))
      (node (ref "T31") (pin "B") (pinfunction "B_B") (pintype "passive"))
    )
    (net (code "119") (name "Net-(R44-Pad2)") (class "Default")
      (node (ref "R44") (pin "2") (pinfunction "2_2") (pintype "passive"))
      (node (ref "T32") (pin "B") (pinfunction "B_B") (pintype "passive"))
    )
    (net (code "120") (name "Net-(R45-Pad2)") (class "Default")
      (node (ref "R45") (pin "2") (pinfunction "2_2") (pintype "passive"))
      (node (ref "T33") (pin "B") (pinfunction "B_B") (pintype "passive"))
    )
    (net (code "121") (name "Net-(R46-Pad2)") (class "Default")
      (node (ref "R46") (pin "2") (pinfunction "2_2") (pintype "passive"))
      (node (ref "T34") (pin "B") (pinfunction "B_B") (pintype "passive"))
    )
    (net (code "122") (name "Net-(R47-Pad2)") (class "Default")
      (node (ref "R47") (pin "2") (pinfunction "2_2") (pintype "passive"))
      (node (ref "T35") (pin "B") (pinfunction "B_B") (pintype "passive"))
    )
    (net (code "123") (name "Net-(T20-PadC)") (class "Default")
      (node (ref "T20") (pin "C") (pinfunction "C_C") (pintype "passive"))
      (node (ref "T21") (pin "B") (pinfunction "B_B") (pintype "passive"))
    )
    (net (code "124") (name "VCC") (class "Default")
      (node (ref "CN1") (pin "2") (pinfunction "2_2") (pintype "passive"))
      (node (ref "CN3") (pin "2") (pinfunction "2_2") (pintype "passive"))
      (node (ref "CN4") (pin "2") (pinfunction "2_2") (pintype "passive"))
      (node (ref "R26") (pin "2") (pinfunction "2_2") (pintype "passive"))
      (node (ref "R31") (pin "2") (pinfunction "2_2") (pintype "passive"))
      (node (ref "R34") (pin "2") (pinfunction "2_2") (pintype "passive"))
      (node (ref "R48") (pin "1") (pinfunction "1_1") (pintype "passive"))
      (node (ref "R49") (pin "1") (pinfunction "1_1") (pintype "passive"))
      (node (ref "R50") (pin "1") (pinfunction "1_1") (pintype "passive"))
      (node (ref "R51") (pin "1") (pinfunction "1_1") (pintype "passive"))
      (node (ref "R52") (pin "1") (pinfunction "1_1") (pintype "passive"))
      (node (ref "R53") (pin "1") (pinfunction "1_1") (pintype "passive"))
      (node (ref "R54") (pin "1") (pinfunction "1_1") (pintype "passive"))
      (node (ref "R55") (pin "1") (pinfunction "1_1") (pintype "passive"))
      (node (ref "R56") (pin "1") (pinfunction "1_1") (pintype "passive"))
      (node (ref "R57") (pin "1") (pinfunction "1_1") (pintype "passive"))
      (node (ref "R58") (pin "1") (pinfunction "1_1") (pintype "passive"))
      (node (ref "R59") (pin "1") (pinfunction "1_1") (pintype "passive"))
      (node (ref "R60") (pin "1") (pinfunction "1_1") (pintype "passive"))
      (node (ref "R61") (pin "1") (pinfunction "1_1") (pintype "passive"))
      (node (ref "R62") (pin "1") (pinfunction "1_1") (pintype "passive"))
      (node (ref "R63") (pin "1") (pinfunction "1_1") (pintype "passive"))
      (node (ref "R64") (pin "1") (pinfunction "1_1") (pintype "passive"))
      (node (ref "R65") (pin "1") (pinfunction "1_1") (pintype "passive"))
      (node (ref "R66") (pin "1") (pinfunction "1_1") (pintype "passive"))
      (node (ref "R67") (pin "1") (pinfunction "1_1") (pintype "passive"))
      (node (ref "R68") (pin "1") (pinfunction "1_1") (pintype "passive"))
      (node (ref "R69") (pin "1") (pinfunction "1_1") (pintype "passive"))
      (node (ref "R70") (pin "1") (pinfunction "1_1") (pintype "passive"))
      (node (ref "R71") (pin "1") (pinfunction "1_1") (pintype "passive"))
      (node (ref "T19") (pin "C") (pinfunction "C_C") (pintype "passive"))
      (node (ref "T21") (pin "E") (pinfunction "E_E") (pintype "passive"))
      (node (ref "T23") (pin "C") (pinfunction "C_C") (pintype "passive"))
      (node (ref "T24") (pin "E") (pinfunction "E_E") (pintype "passive"))
      (node (ref "T25") (pin "E") (pinfunction "E_E") (pintype "passive"))
      (node (ref "T26") (pin "E") (pinfunction "E_E") (pintype "passive"))
      (node (ref "T27") (pin "E") (pinfunction "E_E") (pintype "passive"))
      (node (ref "T28") (pin "E") (pinfunction "E_E") (pintype "passive"))
      (node (ref "T29") (pin "E") (pinfunction "E_E") (pintype "passive"))
    )
  )
)
